# frames_v03.net
KiCad netlist of a schematic drawn in EAGLE
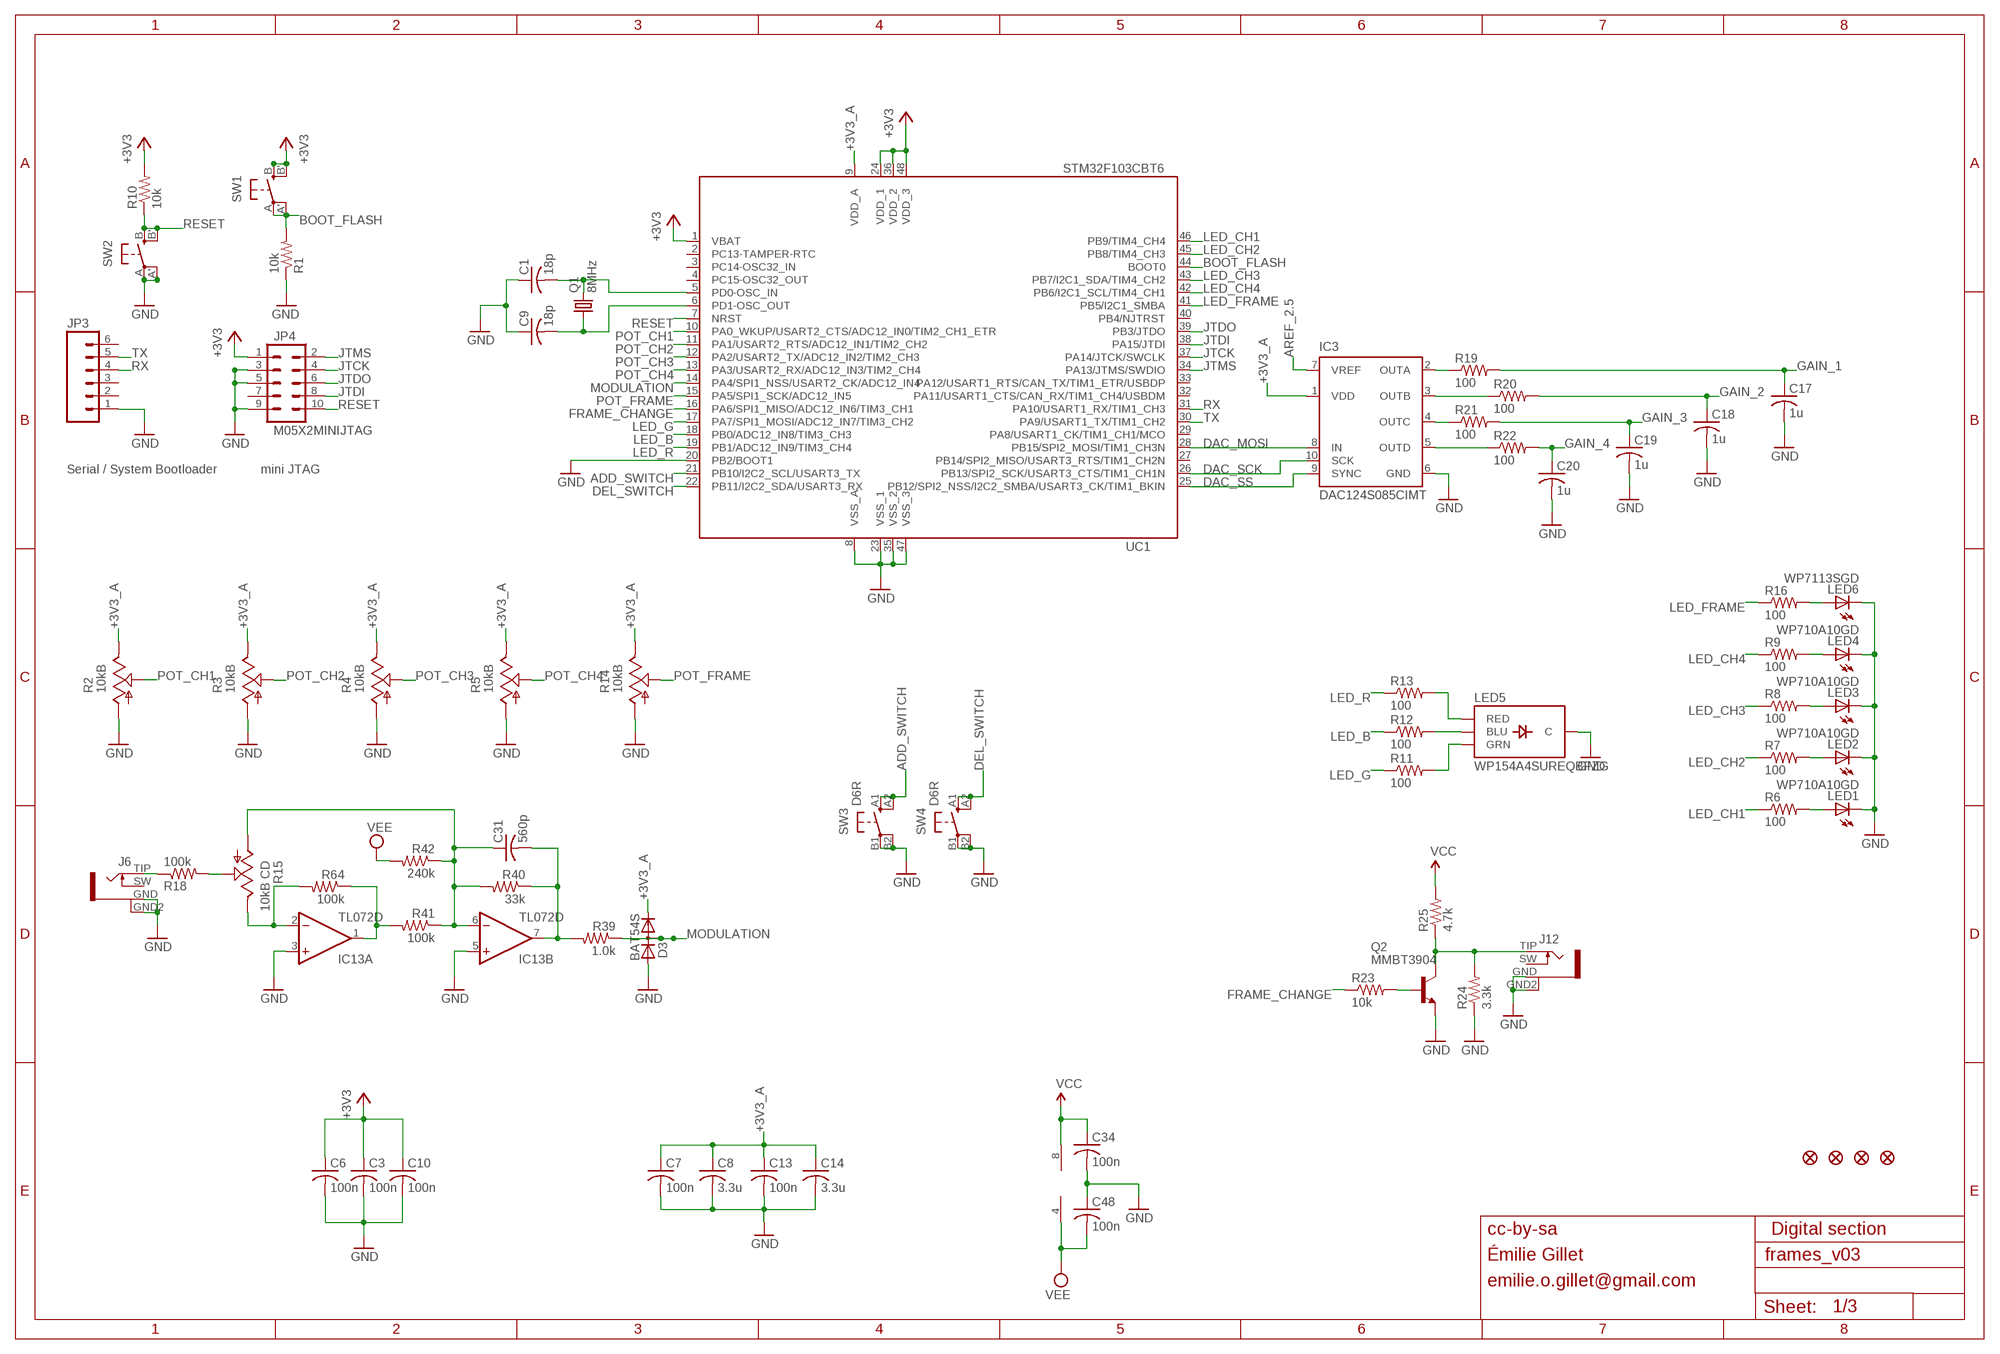
[diagram p0: schematic, sheet 1]
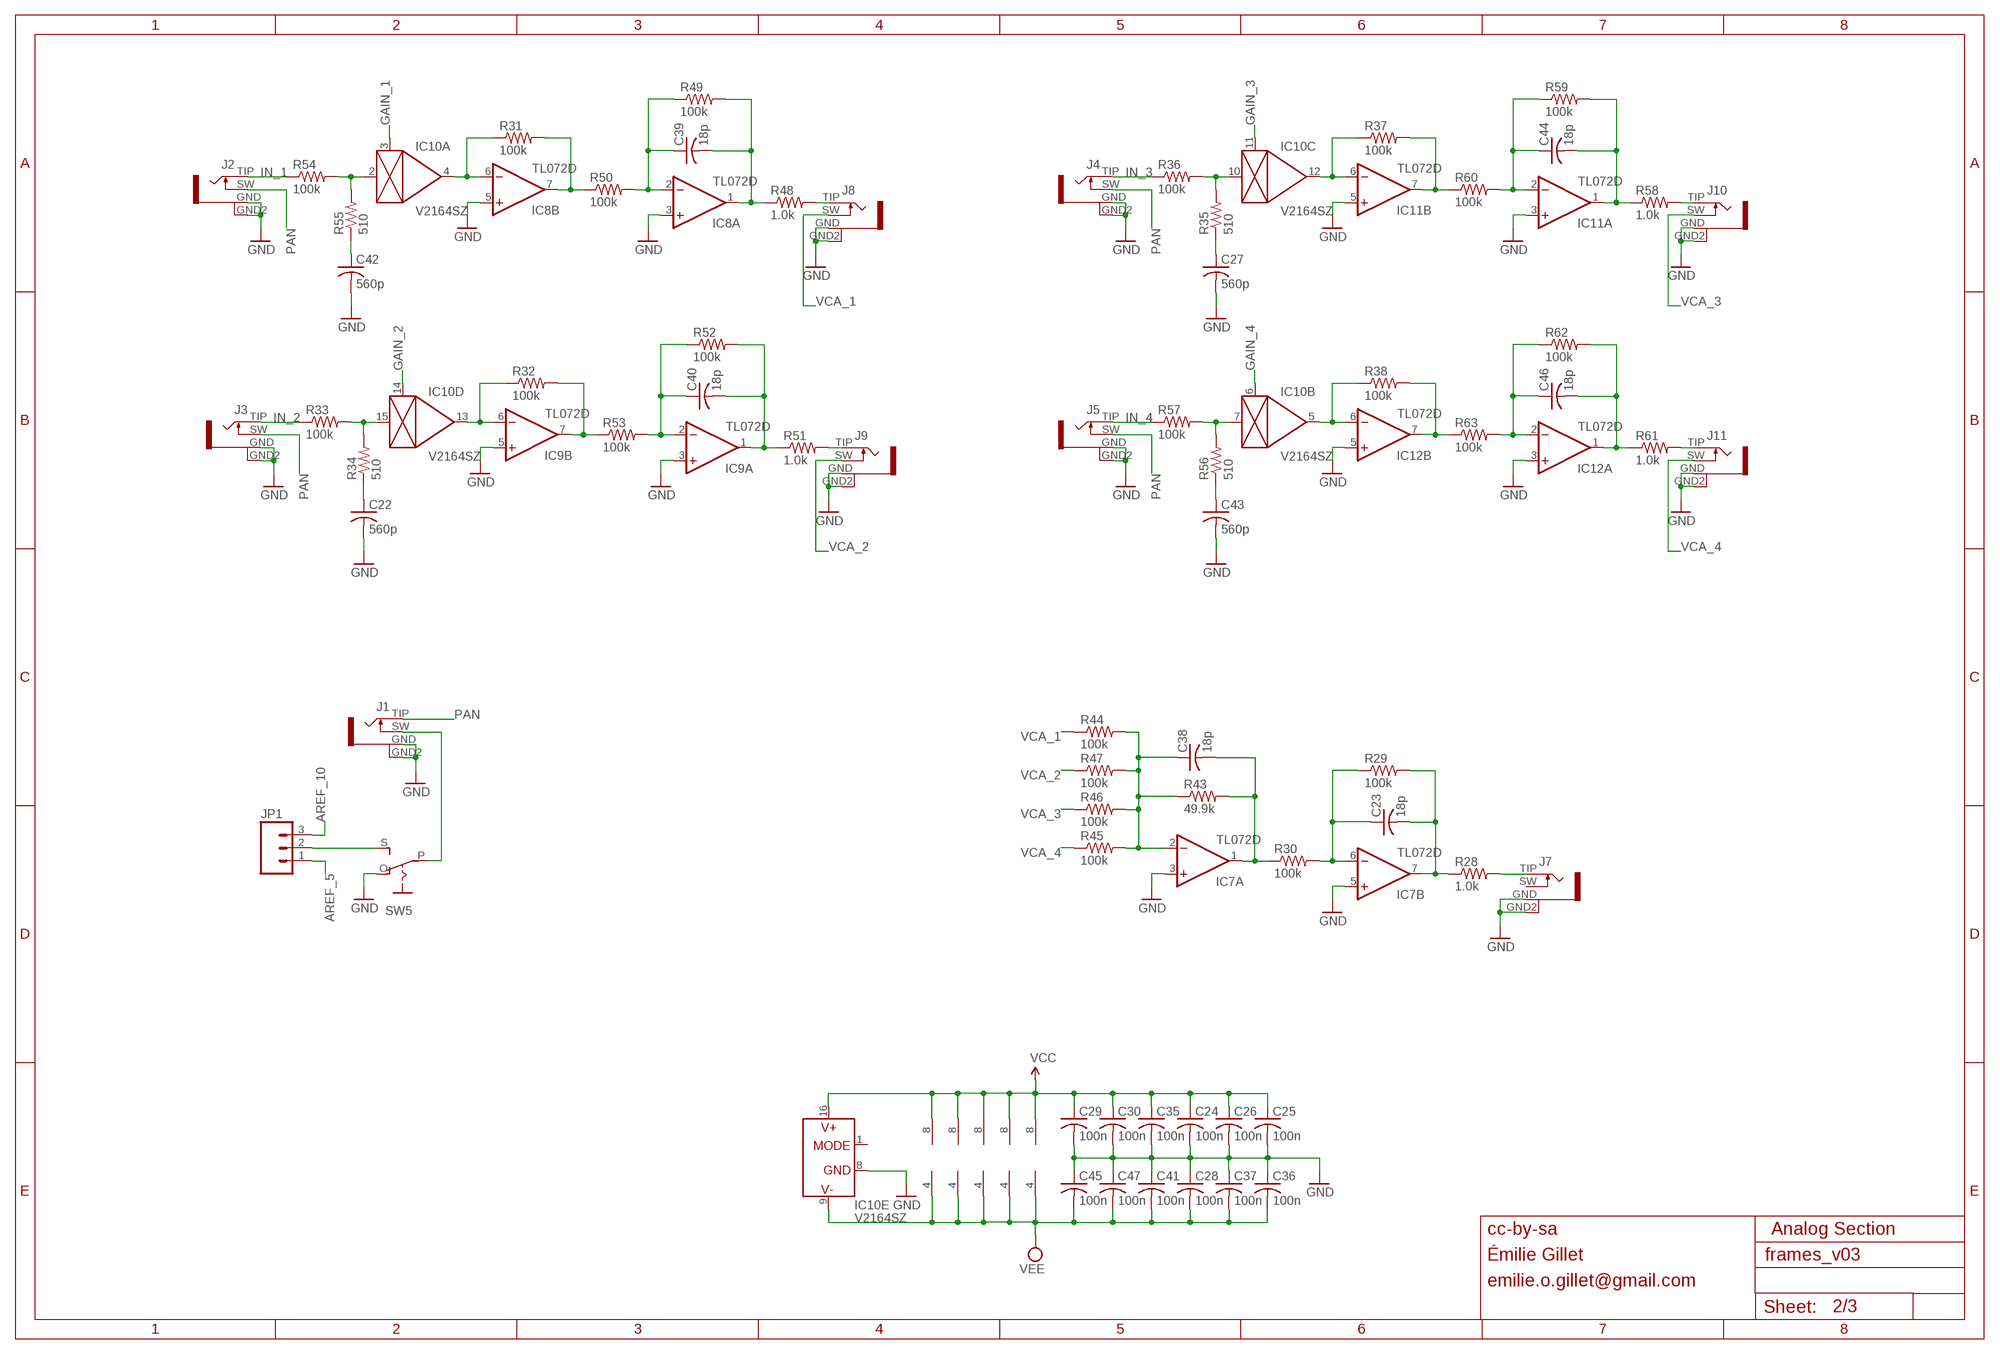
[diagram p1: schematic, sheet 2]
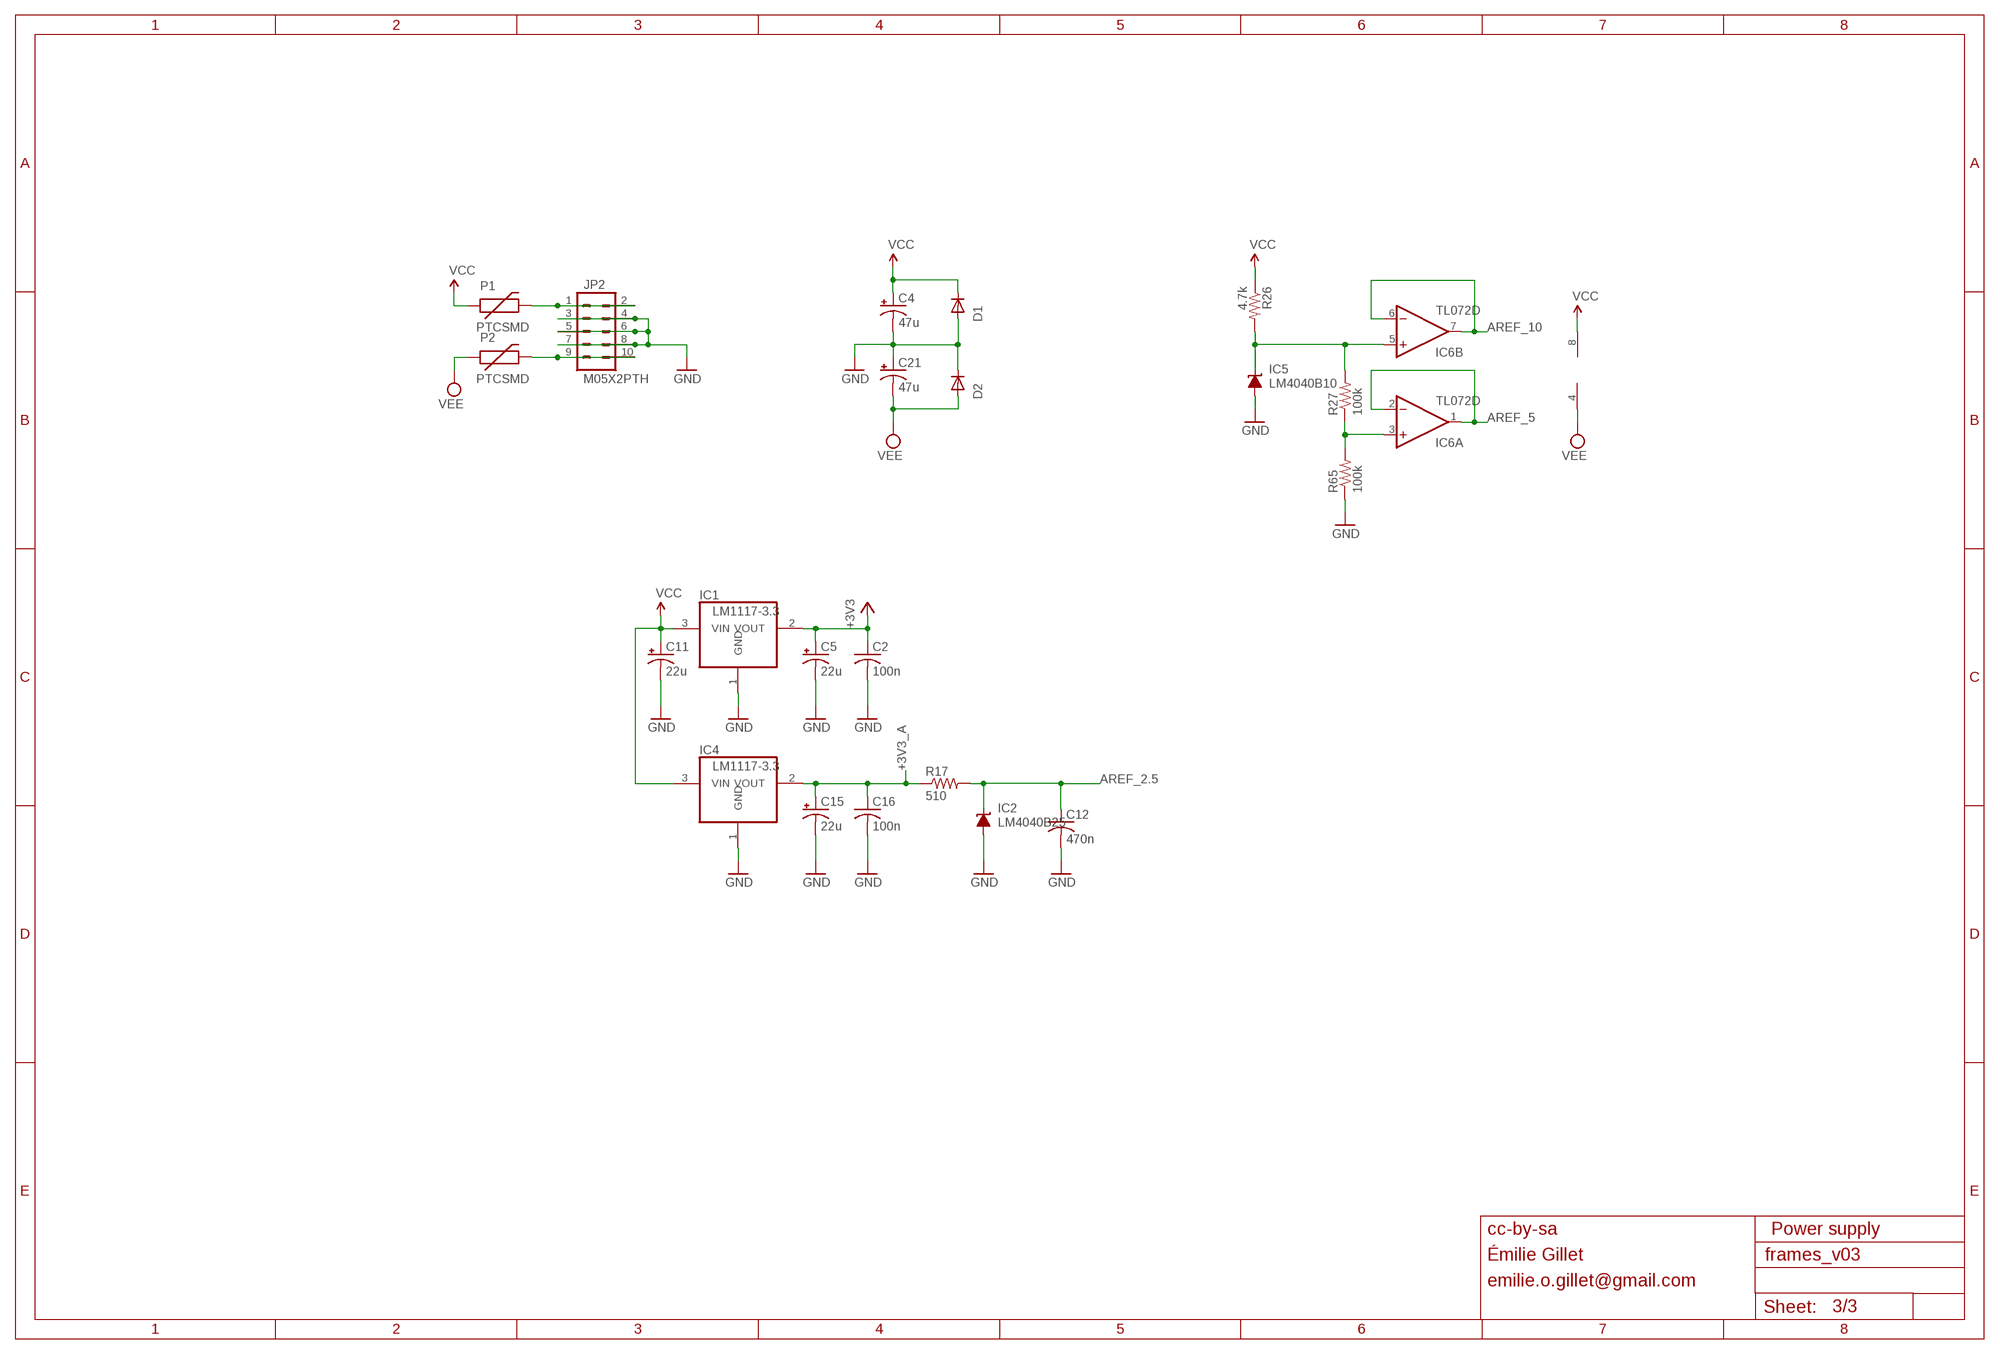
[diagram p2: schematic, sheet 3]

(export (version "E")
  (design (tool "Eeschema 10.0.6"))
  (components
    (comp (ref "C2")
      (value "100n")
      (footprint "eagle-import:C0603")
      (libsource (lib "eagle-import") (part "C-USC0603"))
    )
    (comp (ref "C4")
      (value "47u")
      (footprint "eagle-import:PANASONIC_D")
      (libsource (lib "eagle-import") (part "CPOL-USD"))
    )
    (comp (ref "C5")
      (value "22u")
      (footprint "eagle-import:PANASONIC_C")
      (libsource (lib "eagle-import") (part "CPOL-USC"))
    )
    (comp (ref "C11")
      (value "22u")
      (footprint "eagle-import:PANASONIC_C")
      (libsource (lib "eagle-import") (part "CPOL-USC"))
    )
    (comp (ref "C12")
      (value "470n")
      (footprint "eagle-import:C0603")
      (libsource (lib "eagle-import") (part "C-USC0603"))
    )
    (comp (ref "C15")
      (value "22u")
      (footprint "eagle-import:PANASONIC_C")
      (libsource (lib "eagle-import") (part "CPOL-USC"))
    )
    (comp (ref "C16")
      (value "100n")
      (footprint "eagle-import:C0603")
      (libsource (lib "eagle-import") (part "C-USC0603"))
    )
    (comp (ref "C21")
      (value "47u")
      (footprint "eagle-import:PANASONIC_D")
      (libsource (lib "eagle-import") (part "CPOL-USD"))
    )
    (comp (ref "D1")
      (value "1N5819HW")
      (footprint "eagle-import:SOD123")
      (libsource (lib "eagle-import") (part "DIODE-SOD123"))
    )
    (comp (ref "D2")
      (value "1N5819HW")
      (footprint "eagle-import:SOD123")
      (libsource (lib "eagle-import") (part "DIODE-SOD123"))
    )
    (comp (ref "IC1")
      (value "LM1117-3.3")
      (footprint "eagle-import:SOT223")
      (libsource (lib "eagle-import") (part "REG1117"))
    )
    (comp (ref "IC2")
      (value "LM4040B25")
      (footprint "eagle-import:DBZ_R-PDSO-G3")
      (libsource (lib "eagle-import") (part "LM4041DBZB12"))
    )
    (comp (ref "IC4")
      (value "LM1117-3.3")
      (footprint "eagle-import:SOT223")
      (libsource (lib "eagle-import") (part "REG1117"))
    )
    (comp (ref "IC5")
      (value "LM4040B10")
      (footprint "eagle-import:DBZ_R-PDSO-G3")
      (libsource (lib "eagle-import") (part "LM4041DBZB12"))
    )
    (comp (ref "IC6")
      (value "TL072D")
      (footprint "eagle-import:SO08")
      (libsource (lib "eagle-import") (part "TL072D"))
    )
    (comp (ref "JP2")
      (value "M05X2PTH")
      (footprint "eagle-import:AVR_ICSP")
      (libsource (lib "eagle-import") (part "M05X2PTH"))
    )
    (comp (ref "P1")
      (value "PTCSMD")
      (footprint "eagle-import:PTC-1206")
      (libsource (lib "eagle-import") (part "PTCSMD"))
    )
    (comp (ref "P2")
      (value "PTCSMD")
      (footprint "eagle-import:PTC-1206")
      (libsource (lib "eagle-import") (part "PTCSMD"))
    )
    (comp (ref "R17")
      (value "510")
      (footprint "eagle-import:R0603")
      (libsource (lib "eagle-import") (part "R-US_R0603"))
    )
    (comp (ref "R26")
      (value "4.7k")
      (footprint "eagle-import:R0603")
      (libsource (lib "eagle-import") (part "R-US_R0603"))
    )
    (comp (ref "R27")
      (value "100k")
      (footprint "eagle-import:R0603")
      (libsource (lib "eagle-import") (part "R-US_R0603"))
    )
    (comp (ref "R65")
      (value "100k")
      (footprint "eagle-import:R0603")
      (libsource (lib "eagle-import") (part "R-US_R0603"))
    )
    (comp (ref "C22")
      (value "560p")
      (footprint "eagle-import:C0603")
      (libsource (lib "eagle-import") (part "C-USC0603"))
    )
    (comp (ref "C23")
      (value "18p")
      (footprint "eagle-import:C0603")
      (libsource (lib "eagle-import") (part "C-USC0603"))
    )
    (comp (ref "C24")
      (value "100n")
      (footprint "eagle-import:C0603")
      (libsource (lib "eagle-import") (part "C-USC0603"))
    )
    (comp (ref "C25")
      (value "100n")
      (footprint "eagle-import:C0603")
      (libsource (lib "eagle-import") (part "C-USC0603"))
    )
    (comp (ref "C26")
      (value "100n")
      (footprint "eagle-import:C0603")
      (libsource (lib "eagle-import") (part "C-USC0603"))
    )
    (comp (ref "C27")
      (value "560p")
      (footprint "eagle-import:C0603")
      (libsource (lib "eagle-import") (part "C-USC0603"))
    )
    (comp (ref "C28")
      (value "100n")
      (footprint "eagle-import:C0603")
      (libsource (lib "eagle-import") (part "C-USC0603"))
    )
    (comp (ref "C29")
      (value "100n")
      (footprint "eagle-import:C0603")
      (libsource (lib "eagle-import") (part "C-USC0603"))
    )
    (comp (ref "C30")
      (value "100n")
      (footprint "eagle-import:C0603")
      (libsource (lib "eagle-import") (part "C-USC0603"))
    )
    (comp (ref "C35")
      (value "100n")
      (footprint "eagle-import:C0603")
      (libsource (lib "eagle-import") (part "C-USC0603"))
    )
    (comp (ref "C36")
      (value "100n")
      (footprint "eagle-import:C0603")
      (libsource (lib "eagle-import") (part "C-USC0603"))
    )
    (comp (ref "C37")
      (value "100n")
      (footprint "eagle-import:C0603")
      (libsource (lib "eagle-import") (part "C-USC0603"))
    )
    (comp (ref "C38")
      (value "18p")
      (footprint "eagle-import:C0603")
      (libsource (lib "eagle-import") (part "C-USC0603"))
    )
    (comp (ref "C39")
      (value "18p")
      (footprint "eagle-import:C0603")
      (libsource (lib "eagle-import") (part "C-USC0603"))
    )
    (comp (ref "C40")
      (value "18p")
      (footprint "eagle-import:C0603")
      (libsource (lib "eagle-import") (part "C-USC0603"))
    )
    (comp (ref "C41")
      (value "100n")
      (footprint "eagle-import:C0603")
      (libsource (lib "eagle-import") (part "C-USC0603"))
    )
    (comp (ref "C42")
      (value "560p")
      (footprint "eagle-import:C0603")
      (libsource (lib "eagle-import") (part "C-USC0603"))
    )
    (comp (ref "C43")
      (value "560p")
      (footprint "eagle-import:C0603")
      (libsource (lib "eagle-import") (part "C-USC0603"))
    )
    (comp (ref "C44")
      (value "18p")
      (footprint "eagle-import:C0603")
      (libsource (lib "eagle-import") (part "C-USC0603"))
    )
    (comp (ref "C45")
      (value "100n")
      (footprint "eagle-import:C0603")
      (libsource (lib "eagle-import") (part "C-USC0603"))
    )
    (comp (ref "C46")
      (value "18p")
      (footprint "eagle-import:C0603")
      (libsource (lib "eagle-import") (part "C-USC0603"))
    )
    (comp (ref "C47")
      (value "100n")
      (footprint "eagle-import:C0603")
      (libsource (lib "eagle-import") (part "C-USC0603"))
    )
    (comp (ref "IC7")
      (value "TL072D")
      (footprint "eagle-import:SO08")
      (libsource (lib "eagle-import") (part "og-linear_TL072D"))
    )
    (comp (ref "IC8")
      (value "TL072D")
      (footprint "eagle-import:SO08")
      (libsource (lib "eagle-import") (part "og-linear_TL072D"))
    )
    (comp (ref "IC9")
      (value "TL072D")
      (footprint "eagle-import:SO08")
      (libsource (lib "eagle-import") (part "og-linear_TL072D"))
    )
    (comp (ref "IC10")
      (value "V2164SZ")
      (footprint "eagle-import:SOIC16N")
      (libsource (lib "eagle-import") (part "SSM2164S"))
    )
    (comp (ref "IC11")
      (value "TL072D")
      (footprint "eagle-import:SO08")
      (libsource (lib "eagle-import") (part "og-linear_TL072D"))
    )
    (comp (ref "IC12")
      (value "TL072D")
      (footprint "eagle-import:SO08")
      (libsource (lib "eagle-import") (part "og-linear_TL072D"))
    )
    (comp (ref "J1")
      (value "PJ301WQP")
      (footprint "eagle-import:WQP_PJ_301BM")
      (libsource (lib "eagle-import") (part "PJ301WQP"))
    )
    (comp (ref "J2")
      (value "PJ301WQP")
      (footprint "eagle-import:WQP_PJ_301BM")
      (libsource (lib "eagle-import") (part "PJ301WQP"))
    )
    (comp (ref "J3")
      (value "PJ301WQP")
      (footprint "eagle-import:WQP_PJ_301BM")
      (libsource (lib "eagle-import") (part "PJ301WQP"))
    )
    (comp (ref "J4")
      (value "PJ301WQP")
      (footprint "eagle-import:WQP_PJ_301BM")
      (libsource (lib "eagle-import") (part "PJ301WQP"))
    )
    (comp (ref "J5")
      (value "PJ301WQP")
      (footprint "eagle-import:WQP_PJ_301BM")
      (libsource (lib "eagle-import") (part "PJ301WQP"))
    )
    (comp (ref "J7")
      (value "PJ301WQP")
      (footprint "eagle-import:WQP_PJ_301BM")
      (libsource (lib "eagle-import") (part "PJ301WQP"))
    )
    (comp (ref "J8")
      (value "PJ301WQP")
      (footprint "eagle-import:WQP_PJ_301BM")
      (libsource (lib "eagle-import") (part "PJ301WQP"))
    )
    (comp (ref "J9")
      (value "PJ301WQP")
      (footprint "eagle-import:WQP_PJ_301BM")
      (libsource (lib "eagle-import") (part "PJ301WQP"))
    )
    (comp (ref "J10")
      (value "PJ301WQP")
      (footprint "eagle-import:WQP_PJ_301BM")
      (libsource (lib "eagle-import") (part "PJ301WQP"))
    )
    (comp (ref "J11")
      (value "PJ301WQP")
      (footprint "eagle-import:WQP_PJ_301BM")
      (libsource (lib "eagle-import") (part "PJ301WQP"))
    )
    (comp (ref "JP1")
      (value "M03PTH")
      (footprint "eagle-import:1X03")
      (libsource (lib "eagle-import") (part "M03PTH"))
    )
    (comp (ref "R28")
      (value "1.0k")
      (footprint "eagle-import:R0603")
      (libsource (lib "eagle-import") (part "R-US_R0603"))
    )
    (comp (ref "R29")
      (value "100k")
      (footprint "eagle-import:R0603")
      (libsource (lib "eagle-import") (part "R-US_R0603"))
    )
    (comp (ref "R30")
      (value "100k")
      (footprint "eagle-import:R0603")
      (libsource (lib "eagle-import") (part "R-US_R0603"))
    )
    (comp (ref "R31")
      (value "100k")
      (footprint "eagle-import:R0603")
      (libsource (lib "eagle-import") (part "R-US_R0603"))
    )
    (comp (ref "R32")
      (value "100k")
      (footprint "eagle-import:R0603")
      (libsource (lib "eagle-import") (part "R-US_R0603"))
    )
    (comp (ref "R33")
      (value "100k")
      (footprint "eagle-import:R0603")
      (libsource (lib "eagle-import") (part "R-US_R0603"))
    )
    (comp (ref "R34")
      (value "510")
      (footprint "eagle-import:R0603")
      (libsource (lib "eagle-import") (part "R-US_R0603"))
    )
    (comp (ref "R35")
      (value "510")
      (footprint "eagle-import:R0603")
      (libsource (lib "eagle-import") (part "R-US_R0603"))
    )
    (comp (ref "R36")
      (value "100k")
      (footprint "eagle-import:R0603")
      (libsource (lib "eagle-import") (part "R-US_R0603"))
    )
    (comp (ref "R37")
      (value "100k")
      (footprint "eagle-import:R0603")
      (libsource (lib "eagle-import") (part "R-US_R0603"))
    )
    (comp (ref "R38")
      (value "100k")
      (footprint "eagle-import:R0603")
      (libsource (lib "eagle-import") (part "R-US_R0603"))
    )
    (comp (ref "R43")
      (value "49.9k")
      (footprint "eagle-import:R0603")
      (libsource (lib "eagle-import") (part "R-US_R0603"))
    )
    (comp (ref "R44")
      (value "100k")
      (footprint "eagle-import:R0603")
      (libsource (lib "eagle-import") (part "R-US_R0603"))
    )
    (comp (ref "R45")
      (value "100k")
      (footprint "eagle-import:R0603")
      (libsource (lib "eagle-import") (part "R-US_R0603"))
    )
    (comp (ref "R46")
      (value "100k")
      (footprint "eagle-import:R0603")
      (libsource (lib "eagle-import") (part "R-US_R0603"))
    )
    (comp (ref "R47")
      (value "100k")
      (footprint "eagle-import:R0603")
      (libsource (lib "eagle-import") (part "R-US_R0603"))
    )
    (comp (ref "R48")
      (value "1.0k")
      (footprint "eagle-import:R0603")
      (libsource (lib "eagle-import") (part "R-US_R0603"))
    )
    (comp (ref "R49")
      (value "100k")
      (footprint "eagle-import:R0603")
      (libsource (lib "eagle-import") (part "R-US_R0603"))
    )
    (comp (ref "R50")
      (value "100k")
      (footprint "eagle-import:R0603")
      (libsource (lib "eagle-import") (part "R-US_R0603"))
    )
    (comp (ref "R51")
      (value "1.0k")
      (footprint "eagle-import:R0603")
      (libsource (lib "eagle-import") (part "R-US_R0603"))
    )
    (comp (ref "R52")
      (value "100k")
      (footprint "eagle-import:R0603")
      (libsource (lib "eagle-import") (part "R-US_R0603"))
    )
    (comp (ref "R53")
      (value "100k")
      (footprint "eagle-import:R0603")
      (libsource (lib "eagle-import") (part "R-US_R0603"))
    )
    (comp (ref "R54")
      (value "100k")
      (footprint "eagle-import:R0603")
      (libsource (lib "eagle-import") (part "R-US_R0603"))
    )
    (comp (ref "R55")
      (value "510")
      (footprint "eagle-import:R0603")
      (libsource (lib "eagle-import") (part "R-US_R0603"))
    )
    (comp (ref "R56")
      (value "510")
      (footprint "eagle-import:R0603")
      (libsource (lib "eagle-import") (part "R-US_R0603"))
    )
    (comp (ref "R57")
      (value "100k")
      (footprint "eagle-import:R0603")
      (libsource (lib "eagle-import") (part "R-US_R0603"))
    )
    (comp (ref "R58")
      (value "1.0k")
      (footprint "eagle-import:R0603")
      (libsource (lib "eagle-import") (part "R-US_R0603"))
    )
    (comp (ref "R59")
      (value "100k")
      (footprint "eagle-import:R0603")
      (libsource (lib "eagle-import") (part "R-US_R0603"))
    )
    (comp (ref "R60")
      (value "100k")
      (footprint "eagle-import:R0603")
      (libsource (lib "eagle-import") (part "R-US_R0603"))
    )
    (comp (ref "R61")
      (value "1.0k")
      (footprint "eagle-import:R0603")
      (libsource (lib "eagle-import") (part "R-US_R0603"))
    )
    (comp (ref "R62")
      (value "100k")
      (footprint "eagle-import:R0603")
      (libsource (lib "eagle-import") (part "R-US_R0603"))
    )
    (comp (ref "R63")
      (value "100k")
      (footprint "eagle-import:R0603")
      (libsource (lib "eagle-import") (part "R-US_R0603"))
    )
    (comp (ref "SW5")
      (value "S-ON-ONSMALL_SLIDE")
      (footprint "eagle-import:ES_100SP1T6B11M2QEH_SMALL")
      (libsource (lib "eagle-import") (part "S-ON-ONSMALL_SLIDE"))
    )
    (comp (ref "C1")
      (value "18p")
      (footprint "eagle-import:C0603")
      (libsource (lib "eagle-import") (part "C-USC0603"))
    )
    (comp (ref "C3")
      (value "100n")
      (footprint "eagle-import:C0603")
      (libsource (lib "eagle-import") (part "C-USC0603"))
    )
    (comp (ref "C6")
      (value "100n")
      (footprint "eagle-import:C0603")
      (libsource (lib "eagle-import") (part "C-USC0603"))
    )
    (comp (ref "C7")
      (value "100n")
      (footprint "eagle-import:C0603")
      (libsource (lib "eagle-import") (part "C-USC0603"))
    )
    (comp (ref "C8")
      (value "3.3u")
      (footprint "eagle-import:C0603")
      (libsource (lib "eagle-import") (part "C-USC0603"))
    )
    (comp (ref "C9")
      (value "18p")
      (footprint "eagle-import:C0603")
      (libsource (lib "eagle-import") (part "C-USC0603"))
    )
    (comp (ref "C10")
      (value "100n")
      (footprint "eagle-import:C0603")
      (libsource (lib "eagle-import") (part "C-USC0603"))
    )
    (comp (ref "C13")
      (value "100n")
      (footprint "eagle-import:C0603")
      (libsource (lib "eagle-import") (part "C-USC0603"))
    )
    (comp (ref "C14")
      (value "3.3u")
      (footprint "eagle-import:C0603")
      (libsource (lib "eagle-import") (part "C-USC0603"))
    )
    (comp (ref "C17")
      (value "1u")
      (footprint "eagle-import:C0603")
      (libsource (lib "eagle-import") (part "C-USC0603"))
    )
    (comp (ref "C18")
      (value "1u")
      (footprint "eagle-import:C0603")
      (libsource (lib "eagle-import") (part "C-USC0603"))
    )
    (comp (ref "C19")
      (value "1u")
      (footprint "eagle-import:C0603")
      (libsource (lib "eagle-import") (part "C-USC0603"))
    )
    (comp (ref "C20")
      (value "1u")
      (footprint "eagle-import:C0603")
      (libsource (lib "eagle-import") (part "C-USC0603"))
    )
    (comp (ref "C31")
      (value "560p")
      (footprint "eagle-import:C0603")
      (libsource (lib "eagle-import") (part "C-USC0603"))
    )
    (comp (ref "C34")
      (value "100n")
      (footprint "eagle-import:C0603")
      (libsource (lib "eagle-import") (part "C-USC0603"))
    )
    (comp (ref "C48")
      (value "100n")
      (footprint "eagle-import:C0603")
      (libsource (lib "eagle-import") (part "C-USC0603"))
    )
    (comp (ref "D3")
      (value "BAT54S")
      (footprint "eagle-import:SOT23")
      (libsource (lib "eagle-import") (part "DIODE_2CACA-SOT23"))
    )
    (comp (ref "F1")
      (value "FIDUCIAL1X2")
      (footprint "eagle-import:FIDUCIAL-1X2")
      (libsource (lib "eagle-import") (part "FIDUCIAL1X2"))
    )
    (comp (ref "F2")
      (value "FIDUCIAL1X2")
      (footprint "eagle-import:FIDUCIAL-1X2")
      (libsource (lib "eagle-import") (part "FIDUCIAL1X2"))
    )
    (comp (ref "F3")
      (value "FIDUCIAL1X2")
      (footprint "eagle-import:FIDUCIAL-1X2")
      (libsource (lib "eagle-import") (part "FIDUCIAL1X2"))
    )
    (comp (ref "F4")
      (value "FIDUCIAL1X2")
      (footprint "eagle-import:FIDUCIAL-1X2")
      (libsource (lib "eagle-import") (part "FIDUCIAL1X2"))
    )
    (comp (ref "IC3")
      (value "DAC124S085CIMT")
      (footprint "eagle-import:MSOP10")
      (libsource (lib "eagle-import") (part "DAC124S085CIMT"))
    )
    (comp (ref "IC13")
      (value "TL072D")
      (footprint "eagle-import:SO08")
      (libsource (lib "eagle-import") (part "og-linear_TL072D"))
    )
    (comp (ref "J6")
      (value "PJ301WQP")
      (footprint "eagle-import:WQP_PJ_301BM")
      (libsource (lib "eagle-import") (part "PJ301WQP"))
    )
    (comp (ref "J12")
      (value "PJ301WQP")
      (footprint "eagle-import:WQP_PJ_301BM")
      (libsource (lib "eagle-import") (part "PJ301WQP"))
    )
    (comp (ref "JP3")
      (value "M06SIP")
      (footprint "eagle-import:1X06")
      (libsource (lib "eagle-import") (part "M06SIP"))
    )
    (comp (ref "JP4")
      (value "M05X2MINIJTAG")
      (footprint "eagle-import:2X5-1.27")
      (libsource (lib "eagle-import") (part "M05X2MINIJTAG"))
    )
    (comp (ref "LED1")
      (value "WP710A10GD")
      (footprint "eagle-import:LED3MM")
      (libsource (lib "eagle-import") (part "LED3MM"))
    )
    (comp (ref "LED2")
      (value "WP710A10GD")
      (footprint "eagle-import:LED3MM")
      (libsource (lib "eagle-import") (part "LED3MM"))
    )
    (comp (ref "LED3")
      (value "WP710A10GD")
      (footprint "eagle-import:LED3MM")
      (libsource (lib "eagle-import") (part "LED3MM"))
    )
    (comp (ref "LED4")
      (value "WP710A10GD")
      (footprint "eagle-import:LED3MM")
      (libsource (lib "eagle-import") (part "LED3MM"))
    )
    (comp (ref "LED5")
      (value "WP154A4SUREQBFZG")
      (footprint "eagle-import:LED-TRICOLOR-THROUGHHOLE")
      (libsource (lib "eagle-import") (part "LED-TRICOLOR-THROUGHHOLE"))
    )
    (comp (ref "LED6")
      (value "WP7113SGD")
      (footprint "eagle-import:LED5MM")
      (libsource (lib "eagle-import") (part "LED5MM"))
    )
    (comp (ref "Q1")
      (value "8MHz")
      (footprint "eagle-import:HC49UP")
      (libsource (lib "eagle-import") (part "CRYSTALHC49UP"))
    )
    (comp (ref "Q2")
      (value "MMBT3904")
      (footprint "eagle-import:SOT23-BEC")
      (libsource (lib "eagle-import") (part "-NPN-SOT23-BECMMBT3904LT1"))
    )
    (comp (ref "R1")
      (value "10k")
      (footprint "eagle-import:R0603")
      (libsource (lib "eagle-import") (part "R-US_R0603"))
    )
    (comp (ref "R2")
      (value "10kB")
      (footprint "eagle-import:ALPS_POT_VERTICAL_PS")
      (libsource (lib "eagle-import") (part "POT_USVERTICAL_PS"))
    )
    (comp (ref "R3")
      (value "10kB")
      (footprint "eagle-import:ALPS_POT_VERTICAL_PS")
      (libsource (lib "eagle-import") (part "POT_USVERTICAL_PS"))
    )
    (comp (ref "R4")
      (value "10kB")
      (footprint "eagle-import:ALPS_POT_VERTICAL_PS")
      (libsource (lib "eagle-import") (part "POT_USVERTICAL_PS"))
    )
    (comp (ref "R5")
      (value "10kB")
      (footprint "eagle-import:ALPS_POT_VERTICAL_PS")
      (libsource (lib "eagle-import") (part "POT_USVERTICAL_PS"))
    )
    (comp (ref "R6")
      (value "100")
      (footprint "eagle-import:R0603")
      (libsource (lib "eagle-import") (part "R-US_R0603"))
    )
    (comp (ref "R7")
      (value "100")
      (footprint "eagle-import:R0603")
      (libsource (lib "eagle-import") (part "R-US_R0603"))
    )
    (comp (ref "R8")
      (value "100")
      (footprint "eagle-import:R0603")
      (libsource (lib "eagle-import") (part "R-US_R0603"))
    )
    (comp (ref "R9")
      (value "100")
      (footprint "eagle-import:R0603")
      (libsource (lib "eagle-import") (part "R-US_R0603"))
    )
    (comp (ref "R10")
      (value "10k")
      (footprint "eagle-import:R0603")
      (libsource (lib "eagle-import") (part "R-US_R0603"))
    )
    (comp (ref "R11")
      (value "100")
      (footprint "eagle-import:R0603")
      (libsource (lib "eagle-import") (part "R-US_R0603"))
    )
    (comp (ref "R12")
      (value "100")
      (footprint "eagle-import:R0603")
      (libsource (lib "eagle-import") (part "R-US_R0603"))
    )
    (comp (ref "R13")
      (value "100")
      (footprint "eagle-import:R0603")
      (libsource (lib "eagle-import") (part "R-US_R0603"))
    )
    (comp (ref "R14")
      (value "10kB")
      (footprint "eagle-import:ALPS_POT_VERTICAL_PS")
      (libsource (lib "eagle-import") (part "POT_USVERTICAL_PS"))
    )
    (comp (ref "R15")
      (value "10kB CD")
      (footprint "eagle-import:ALPS_POT_VERTICAL_PS")
      (libsource (lib "eagle-import") (part "POT_USVERTICAL_PS"))
    )
    (comp (ref "R16")
      (value "100")
      (footprint "eagle-import:R0603")
      (libsource (lib "eagle-import") (part "R-US_R0603"))
    )
    (comp (ref "R18")
      (value "100k")
      (footprint "eagle-import:R0603")
      (libsource (lib "eagle-import") (part "R-US_R0603"))
    )
    (comp (ref "R19")
      (value "100")
      (footprint "eagle-import:R0603")
      (libsource (lib "eagle-import") (part "R-US_R0603"))
    )
    (comp (ref "R20")
      (value "100")
      (footprint "eagle-import:R0603")
      (libsource (lib "eagle-import") (part "R-US_R0603"))
    )
    (comp (ref "R21")
      (value "100")
      (footprint "eagle-import:R0603")
      (libsource (lib "eagle-import") (part "R-US_R0603"))
    )
    (comp (ref "R22")
      (value "100")
      (footprint "eagle-import:R0603")
      (libsource (lib "eagle-import") (part "R-US_R0603"))
    )
    (comp (ref "R23")
      (value "10k")
      (footprint "eagle-import:R0603")
      (libsource (lib "eagle-import") (part "R-US_R0603"))
    )
    (comp (ref "R24")
      (value "3.3k")
      (footprint "eagle-import:R0603")
      (libsource (lib "eagle-import") (part "R-US_R0603"))
    )
    (comp (ref "R25")
      (value "4.7k")
      (footprint "eagle-import:R0603")
      (libsource (lib "eagle-import") (part "R-US_R0603"))
    )
    (comp (ref "R39")
      (value "1.0k")
      (footprint "eagle-import:R0603")
      (libsource (lib "eagle-import") (part "R-US_R0603"))
    )
    (comp (ref "R40")
      (value "33k")
      (footprint "eagle-import:R0603")
      (libsource (lib "eagle-import") (part "R-US_R0603"))
    )
    (comp (ref "R41")
      (value "100k")
      (footprint "eagle-import:R0603")
      (libsource (lib "eagle-import") (part "R-US_R0603"))
    )
    (comp (ref "R42")
      (value "240k")
      (footprint "eagle-import:R0603")
      (libsource (lib "eagle-import") (part "R-US_R0603"))
    )
    (comp (ref "R64")
      (value "100k")
      (footprint "eagle-import:R0603")
      (libsource (lib "eagle-import") (part "R-US_R0603"))
    )
    (comp (ref "SW1")
      (value "EVQQ2")
      (footprint "eagle-import:EVQ-Q2")
      (libsource (lib "eagle-import") (part "EVQQ2"))
    )
    (comp (ref "SW2")
      (value "EVQQ2")
      (footprint "eagle-import:EVQ-Q2")
      (libsource (lib "eagle-import") (part "EVQQ2"))
    )
    (comp (ref "SW3")
      (value "D6R")
      (footprint "eagle-import:D6R")
      (libsource (lib "eagle-import") (part "D6R"))
    )
    (comp (ref "SW4")
      (value "D6R")
      (footprint "eagle-import:D6R")
      (libsource (lib "eagle-import") (part "D6R"))
    )
    (comp (ref "UC1")
      (value "STM32F103CBT6")
      (footprint "eagle-import:LQFP48")
      (libsource (lib "eagle-import") (part "STM32F103CB"))
    )
  )
  (nets
    (net (code "1") (name "+3V3") (class "Default")
      (node (ref "C10") (pin "1") (pinfunction "1_1") (pintype "passive"))
      (node (ref "C2") (pin "1") (pinfunction "1_1") (pintype "passive"))
      (node (ref "C3") (pin "1") (pinfunction "1_1") (pintype "passive"))
      (node (ref "C5") (pin "+") (pinfunction "+_+") (pintype "passive"))
      (node (ref "C6") (pin "1") (pinfunction "1_1") (pintype "passive"))
      (node (ref "IC1") (pin "2") (pinfunction "VOUT_2") (pintype "output"))
      (node (ref "JP4") (pin "1") (pinfunction "1_1") (pintype "passive"))
      (node (ref "R10") (pin "2") (pinfunction "2_2") (pintype "passive"))
      (node (ref "SW1") (pin "B") (pinfunction "S_B") (pintype "passive"))
      (node (ref "SW1") (pin "B'") (pinfunction "S1_B'") (pintype "passive"))
      (node (ref "UC1") (pin "1") (pinfunction "VBAT_1") (pintype "power_in"))
      (node (ref "UC1") (pin "24") (pinfunction "VDD_1_24") (pintype "power_in"))
      (node (ref "UC1") (pin "36") (pinfunction "VDD_2_36") (pintype "power_in"))
      (node (ref "UC1") (pin "48") (pinfunction "VDD_3_48") (pintype "power_in"))
    )
    (net (code "2") (name "+3V3_A") (class "Default")
      (node (ref "C13") (pin "1") (pinfunction "1_1") (pintype "passive"))
      (node (ref "C14") (pin "1") (pinfunction "1_1") (pintype "passive"))
      (node (ref "C15") (pin "+") (pinfunction "+_+") (pintype "passive"))
      (node (ref "C16") (pin "1") (pinfunction "1_1") (pintype "passive"))
      (node (ref "C7") (pin "1") (pinfunction "1_1") (pintype "passive"))
      (node (ref "C8") (pin "1") (pinfunction "1_1") (pintype "passive"))
      (node (ref "D3") (pin "2") (pinfunction "C_2") (pintype "passive"))
      (node (ref "IC3") (pin "1") (pinfunction "VDD_1") (pintype "power_in"))
      (node (ref "IC4") (pin "2") (pinfunction "VOUT_2") (pintype "output"))
      (node (ref "R14") (pin "P$1") (pinfunction "E_P$1") (pintype "passive"))
      (node (ref "R17") (pin "1") (pinfunction "1_1") (pintype "passive"))
      (node (ref "R2") (pin "P$1") (pinfunction "E_P$1") (pintype "passive"))
      (node (ref "R3") (pin "P$1") (pinfunction "E_P$1") (pintype "passive"))
      (node (ref "R4") (pin "P$1") (pinfunction "E_P$1") (pintype "passive"))
      (node (ref "R5") (pin "P$1") (pinfunction "E_P$1") (pintype "passive"))
      (node (ref "UC1") (pin "9") (pinfunction "VDD_A_9") (pintype "power_in"))
    )
    (net (code "3") (name "ADD_SWITCH") (class "Default")
      (node (ref "SW3") (pin "A1") (pinfunction "S_A1") (pintype "passive"))
      (node (ref "SW3") (pin "A2") (pinfunction "S1_A2") (pintype "passive"))
      (node (ref "UC1") (pin "21") (pinfunction "PB10/I2C2_SCL/USART3_TX_21") (pintype "input"))
    )
    (net (code "4") (name "AREF_2.5") (class "Default")
      (node (ref "C12") (pin "1") (pinfunction "1_1") (pintype "passive"))
      (node (ref "IC2") (pin "1") (pinfunction "C_1") (pintype "passive"))
      (node (ref "IC3") (pin "7") (pinfunction "VREF_7") (pintype "bidirectional"))
      (node (ref "R17") (pin "2") (pinfunction "2_2") (pintype "passive"))
    )
    (net (code "5") (name "AREF_5") (class "Default")
      (node (ref "IC6") (pin "1") (pinfunction "OUT_1") (pintype "output"))
      (node (ref "IC6") (pin "2") (pinfunction "-IN_2") (pintype "input"))
      (node (ref "JP1") (pin "1") (pinfunction "1_1") (pintype "passive"))
    )
    (net (code "6") (name "AREF_10") (class "Default")
      (node (ref "IC6") (pin "6") (pinfunction "-IN_6") (pintype "input"))
      (node (ref "IC6") (pin "7") (pinfunction "OUT_7") (pintype "output"))
      (node (ref "JP1") (pin "3") (pinfunction "3_3") (pintype "passive"))
    )
    (net (code "7") (name "BOOT_FLASH") (class "Default")
      (node (ref "R1") (pin "2") (pinfunction "2_2") (pintype "passive"))
      (node (ref "SW1") (pin "A") (pinfunction "P_A") (pintype "passive"))
      (node (ref "SW1") (pin "A'") (pinfunction "P1_A'") (pintype "passive"))
      (node (ref "UC1") (pin "44") (pinfunction "BOOT0_44") (pintype "input"))
    )
    (net (code "8") (name "DAC_MOSI") (class "Default")
      (node (ref "IC3") (pin "8") (pinfunction "IN_8") (pintype "input"))
      (node (ref "UC1") (pin "28") (pinfunction "PB15/SPI2_MOSI/TIM1_CH3N_28") (pintype "input"))
    )
    (net (code "9") (name "DAC_SCK") (class "Default")
      (node (ref "IC3") (pin "10") (pinfunction "SCK_10") (pintype "input"))
      (node (ref "UC1") (pin "26") (pinfunction "PB13/SPI2_SCK/USART3_CTS/TIM1_CH1N_26") (pintype "input"))
    )
    (net (code "10") (name "DAC_SS") (class "Default")
      (node (ref "IC3") (pin "9") (pinfunction "SYNC_9") (pintype "input"))
      (node (ref "UC1") (pin "25") (pinfunction "PB12/SPI2_NSS/I2C2_SMBA/USART3_CK/TIM1_BKIN_25") (pintype "input"))
    )
    (net (code "11") (name "DEL_SWITCH") (class "Default")
      (node (ref "SW4") (pin "A1") (pinfunction "S_A1") (pintype "passive"))
      (node (ref "SW4") (pin "A2") (pinfunction "S1_A2") (pintype "passive"))
      (node (ref "UC1") (pin "22") (pinfunction "PB11/I2C2_SDA/USART3_RX_22") (pintype "input"))
    )
    (net (code "12") (name "FRAME_CHANGE") (class "Default")
      (node (ref "R23") (pin "1") (pinfunction "1_1") (pintype "passive"))
      (node (ref "UC1") (pin "16") (pinfunction "PA6/SPI1_MISO/ADC12_IN6/TIM3_CH1_16") (pintype "bidirectional"))
    )
    (net (code "13") (name "GAIN_1") (class "Default")
      (node (ref "C17") (pin "1") (pinfunction "1_1") (pintype "passive"))
      (node (ref "IC10") (pin "3") (pinfunction "CTRL_3") (pintype "input"))
      (node (ref "R19") (pin "2") (pinfunction "2_2") (pintype "passive"))
    )
    (net (code "14") (name "GAIN_2") (class "Default")
      (node (ref "C18") (pin "1") (pinfunction "1_1") (pintype "passive"))
      (node (ref "IC10") (pin "14") (pinfunction "CTRL_14") (pintype "input"))
      (node (ref "R20") (pin "2") (pinfunction "2_2") (pintype "passive"))
    )
    (net (code "15") (name "GAIN_3") (class "Default")
      (node (ref "C19") (pin "1") (pinfunction "1_1") (pintype "passive"))
      (node (ref "IC10") (pin "11") (pinfunction "CTRL_11") (pintype "input"))
      (node (ref "R21") (pin "2") (pinfunction "2_2") (pintype "passive"))
    )
    (net (code "16") (name "GAIN_4") (class "Default")
      (node (ref "C20") (pin "1") (pinfunction "1_1") (pintype "passive"))
      (node (ref "IC10") (pin "6") (pinfunction "CTRL_6") (pintype "input"))
      (node (ref "R22") (pin "2") (pinfunction "2_2") (pintype "passive"))
    )
    (net (code "17") (name "GND") (class "Default")
      (node (ref "C1") (pin "1") (pinfunction "1_1") (pintype "passive"))
      (node (ref "C10") (pin "2") (pinfunction "2_2") (pintype "passive"))
      (node (ref "C11") (pin "-") (pinfunction "-_-") (pintype "passive"))
      (node (ref "C12") (pin "2") (pinfunction "2_2") (pintype "passive"))
      (node (ref "C13") (pin "2") (pinfunction "2_2") (pintype "passive"))
      (node (ref "C14") (pin "2") (pinfunction "2_2") (pintype "passive"))
      (node (ref "C15") (pin "-") (pinfunction "-_-") (pintype "passive"))
      (node (ref "C16") (pin "2") (pinfunction "2_2") (pintype "passive"))
      (node (ref "C17") (pin "2") (pinfunction "2_2") (pintype "passive"))
      (node (ref "C18") (pin "2") (pinfunction "2_2") (pintype "passive"))
      (node (ref "C19") (pin "2") (pinfunction "2_2") (pintype "passive"))
      (node (ref "C2") (pin "2") (pinfunction "2_2") (pintype "passive"))
      (node (ref "C20") (pin "2") (pinfunction "2_2") (pintype "passive"))
      (node (ref "C21") (pin "+") (pinfunction "+_+") (pintype "passive"))
      (node (ref "C22") (pin "2") (pinfunction "2_2") (pintype "passive"))
      (node (ref "C24") (pin "2") (pinfunction "2_2") (pintype "passive"))
      (node (ref "C25") (pin "2") (pinfunction "2_2") (pintype "passive"))
      (node (ref "C26") (pin "2") (pinfunction "2_2") (pintype "passive"))
      (node (ref "C27") (pin "2") (pinfunction "2_2") (pintype "passive"))
      (node (ref "C28") (pin "1") (pinfunction "1_1") (pintype "passive"))
      (node (ref "C29") (pin "2") (pinfunction "2_2") (pintype "passive"))
      (node (ref "C3") (pin "2") (pinfunction "2_2") (pintype "passive"))
      (node (ref "C30") (pin "2") (pinfunction "2_2") (pintype "passive"))
      (node (ref "C34") (pin "2") (pinfunction "2_2") (pintype "passive"))
      (node (ref "C35") (pin "2") (pinfunction "2_2") (pintype "passive"))
      (node (ref "C36") (pin "1") (pinfunction "1_1") (pintype "passive"))
      (node (ref "C37") (pin "1") (pinfunction "1_1") (pintype "passive"))
      (node (ref "C4") (pin "-") (pinfunction "-_-") (pintype "passive"))
      (node (ref "C41") (pin "1") (pinfunction "1_1") (pintype "passive"))
      (node (ref "C42") (pin "2") (pinfunction "2_2") (pintype "passive"))
      (node (ref "C43") (pin "2") (pinfunction "2_2") (pintype "passive"))
      (node (ref "C45") (pin "1") (pinfunction "1_1") (pintype "passive"))
      (node (ref "C47") (pin "1") (pinfunction "1_1") (pintype "passive"))
      (node (ref "C48") (pin "1") (pinfunction "1_1") (pintype "passive"))
      (node (ref "C5") (pin "-") (pinfunction "-_-") (pintype "passive"))
      (node (ref "C6") (pin "2") (pinfunction "2_2") (pintype "passive"))
      (node (ref "C7") (pin "2") (pinfunction "2_2") (pintype "passive"))
      (node (ref "C8") (pin "2") (pinfunction "2_2") (pintype "passive"))
      (node (ref "C9") (pin "1") (pinfunction "1_1") (pintype "passive"))
      (node (ref "D1") (pin "A") (pinfunction "A_A") (pintype "passive"))
      (node (ref "D2") (pin "C") (pinfunction "C_C") (pintype "passive"))
      (node (ref "D3") (pin "1") (pinfunction "A_1") (pintype "passive"))
      (node (ref "IC1") (pin "1") (pinfunction "GND_1") (pintype "power_in"))
      (node (ref "IC10") (pin "8") (pinfunction "GND_8") (pintype "power_in"))
      (node (ref "IC11") (pin "3") (pinfunction "+IN_3") (pintype "input"))
      (node (ref "IC11") (pin "5") (pinfunction "+IN_5") (pintype "input"))
      (node (ref "IC12") (pin "3") (pinfunction "+IN_3") (pintype "input"))
      (node (ref "IC12") (pin "5") (pinfunction "+IN_5") (pintype "input"))
      (node (ref "IC13") (pin "3") (pinfunction "+IN_3") (pintype "input"))
      (node (ref "IC13") (pin "5") (pinfunction "+IN_5") (pintype "input"))
      (node (ref "IC2") (pin "2") (pinfunction "A_2") (pintype "passive"))
      (node (ref "IC3") (pin "6") (pinfunction "GND_6") (pintype "power_in"))
      (node (ref "IC4") (pin "1") (pinfunction "GND_1") (pintype "power_in"))
      (node (ref "IC5") (pin "2") (pinfunction "A_2") (pintype "passive"))
      (node (ref "IC7") (pin "3") (pinfunction "+IN_3") (pintype "input"))
      (node (ref "IC7") (pin "5") (pinfunction "+IN_5") (pintype "input"))
      (node (ref "IC8") (pin "3") (pinfunction "+IN_3") (pintype "input"))
      (node (ref "IC8") (pin "5") (pinfunction "+IN_5") (pintype "input"))
      (node (ref "IC9") (pin "3") (pinfunction "+IN_3") (pintype "input"))
      (node (ref "IC9") (pin "5") (pinfunction "+IN_5") (pintype "input"))
      (node (ref "J1") (pin "GND") (pinfunction "1_GND") (pintype "passive"))
      (node (ref "J1") (pin "GND2") (pinfunction "4_GND2") (pintype "passive"))
      (node (ref "J10") (pin "GND") (pinfunction "1_GND") (pintype "passive"))
      (node (ref "J10") (pin "GND2") (pinfunction "4_GND2") (pintype "passive"))
      (node (ref "J11") (pin "GND") (pinfunction "1_GND") (pintype "passive"))
      (node (ref "J11") (pin "GND2") (pinfunction "4_GND2") (pintype "passive"))
      (node (ref "J12") (pin "GND") (pinfunction "1_GND") (pintype "passive"))
      (node (ref "J12") (pin "GND2") (pinfunction "4_GND2") (pintype "passive"))
      (node (ref "J2") (pin "GND") (pinfunction "1_GND") (pintype "passive"))
      (node (ref "J2") (pin "GND2") (pinfunction "4_GND2") (pintype "passive"))
      (node (ref "J3") (pin "GND") (pinfunction "1_GND") (pintype "passive"))
      (node (ref "J3") (pin "GND2") (pinfunction "4_GND2") (pintype "passive"))
      (node (ref "J4") (pin "GND") (pinfunction "1_GND") (pintype "passive"))
      (node (ref "J4") (pin "GND2") (pinfunction "4_GND2") (pintype "passive"))
      (node (ref "J5") (pin "GND") (pinfunction "1_GND") (pintype "passive"))
      (node (ref "J5") (pin "GND2") (pinfunction "4_GND2") (pintype "passive"))
      (node (ref "J6") (pin "GND") (pinfunction "1_GND") (pintype "passive"))
      (node (ref "J6") (pin "GND2") (pinfunction "4_GND2") (pintype "passive"))
      (node (ref "J7") (pin "GND") (pinfunction "1_GND") (pintype "passive"))
      (node (ref "J7") (pin "GND2") (pinfunction "4_GND2") (pintype "passive"))
      (node (ref "J8") (pin "GND") (pinfunction "1_GND") (pintype "passive"))
      (node (ref "J8") (pin "GND2") (pinfunction "4_GND2") (pintype "passive"))
      (node (ref "J9") (pin "GND") (pinfunction "1_GND") (pintype "passive"))
      (node (ref "J9") (pin "GND2") (pinfunction "4_GND2") (pintype "passive"))
      (node (ref "JP2") (pin "3") (pinfunction "3_3") (pintype "passive"))
      (node (ref "JP2") (pin "4") (pinfunction "4_4") (pintype "passive"))
      (node (ref "JP2") (pin "5") (pinfunction "5_5") (pintype "passive"))
      (node (ref "JP2") (pin "6") (pinfunction "6_6") (pintype "passive"))
      (node (ref "JP2") (pin "7") (pinfunction "7_7") (pintype "passive"))
      (node (ref "JP2") (pin "8") (pinfunction "8_8") (pintype "passive"))
      (node (ref "JP3") (pin "1") (pinfunction "1_1") (pintype "passive"))
      (node (ref "JP4") (pin "3") (pinfunction "3_3") (pintype "passive"))
      (node (ref "JP4") (pin "5") (pinfunction "5_5") (pintype "passive"))
      (node (ref "JP4") (pin "9") (pinfunction "9_9") (pintype "passive"))
      (node (ref "LED1") (pin "K") (pinfunction "C_K") (pintype "passive"))
      (node (ref "LED2") (pin "K") (pinfunction "C_K") (pintype "passive"))
      (node (ref "LED3") (pin "K") (pinfunction "C_K") (pintype "passive"))
      (node (ref "LED4") (pin "K") (pinfunction "C_K") (pintype "passive"))
      (node (ref "LED5") (pin "GND") (pinfunction "C_GND") (pintype "bidirectional"))
      (node (ref "LED6") (pin "K") (pinfunction "C_K") (pintype "passive"))
      (node (ref "Q2") (pin "E") (pinfunction "E_E") (pintype "passive"))
      (node (ref "R1") (pin "1") (pinfunction "1_1") (pintype "passive"))
      (node (ref "R14") (pin "P$3") (pinfunction "A_P$3") (pintype "passive"))
      (node (ref "R2") (pin "P$3") (pinfunction "A_P$3") (pintype "passive"))
      (node (ref "R24") (pin "1") (pinfunction "1_1") (pintype "passive"))
      (node (ref "R3") (pin "P$3") (pinfunction "A_P$3") (pintype "passive"))
      (node (ref "R4") (pin "P$3") (pinfunction "A_P$3") (pintype "passive"))
      (node (ref "R5") (pin "P$3") (pinfunction "A_P$3") (pintype "passive"))
      (node (ref "R65") (pin "1") (pinfunction "1_1") (pintype "passive"))
      (node (ref "SW2") (pin "A") (pinfunction "P_A") (pintype "passive"))
      (node (ref "SW2") (pin "A'") (pinfunction "P1_A'") (pintype "passive"))
      (node (ref "SW3") (pin "B1") (pinfunction "P_B1") (pintype "passive"))
      (node (ref "SW3") (pin "B2") (pinfunction "P1_B2") (pintype "passive"))
      (node (ref "SW4") (pin "B1") (pinfunction "P_B1") (pintype "passive"))
      (node (ref "SW4") (pin "B2") (pinfunction "P1_B2") (pintype "passive"))
      (node (ref "SW5") (pin "O") (pinfunction "O_O") (pintype "passive"))
      (node (ref "UC1") (pin "20") (pinfunction "PB2/BOOT1_20") (pintype "bidirectional"))
      (node (ref "UC1") (pin "23") (pinfunction "VSS_1_23") (pintype "power_in"))
      (node (ref "UC1") (pin "35") (pinfunction "VSS_2_35") (pintype "power_in"))
      (node (ref "UC1") (pin "47") (pinfunction "VSS_3_47") (pintype "power_in"))
      (node (ref "UC1") (pin "8") (pinfunction "VSS_A_8") (pintype "power_in"))
    )
    (net (code "18") (name "IN_1") (class "Default")
      (node (ref "J2") (pin "TIP") (pinfunction "2_TIP") (pintype "passive"))
      (node (ref "R54") (pin "1") (pinfunction "1_1") (pintype "passive"))
    )
    (net (code "19") (name "IN_2") (class "Default")
      (node (ref "J3") (pin "TIP") (pinfunction "2_TIP") (pintype "passive"))
      (node (ref "R33") (pin "1") (pinfunction "1_1") (pintype "passive"))
    )
    (net (code "20") (name "IN_3") (class "Default")
      (node (ref "J4") (pin "TIP") (pinfunction "2_TIP") (pintype "passive"))
      (node (ref "R36") (pin "1") (pinfunction "1_1") (pintype "passive"))
    )
    (net (code "21") (name "IN_4") (class "Default")
      (node (ref "J5") (pin "TIP") (pinfunction "2_TIP") (pintype "passive"))
      (node (ref "R57") (pin "1") (pinfunction "1_1") (pintype "passive"))
    )
    (net (code "22") (name "JTCK") (class "Default")
      (node (ref "JP4") (pin "4") (pinfunction "4_4") (pintype "passive"))
      (node (ref "UC1") (pin "37") (pinfunction "PA14/JTCK/SWCLK_37") (pintype "bidirectional"))
    )
    (net (code "23") (name "JTDI") (class "Default")
      (node (ref "JP4") (pin "8") (pinfunction "8_8") (pintype "passive"))
      (node (ref "UC1") (pin "38") (pinfunction "PA15/JTDI_38") (pintype "bidirectional"))
    )
    (net (code "24") (name "JTDO") (class "Default")
      (node (ref "JP4") (pin "6") (pinfunction "6_6") (pintype "passive"))
      (node (ref "UC1") (pin "39") (pinfunction "PB3/JTDO_39") (pintype "bidirectional"))
    )
    (net (code "25") (name "JTMS") (class "Default")
      (node (ref "JP4") (pin "2") (pinfunction "2_2") (pintype "passive"))
      (node (ref "UC1") (pin "34") (pinfunction "PA13/JTMS/SWDIO_34") (pintype "bidirectional"))
    )
    (net (code "26") (name "LED_B") (class "Default")
      (node (ref "R12") (pin "1") (pinfunction "1_1") (pintype "passive"))
      (node (ref "UC1") (pin "18") (pinfunction "PB0/ADC12_IN8/TIM3_CH3_18") (pintype "bidirectional"))
    )
    (net (code "27") (name "LED_CH1") (class "Default")
      (node (ref "R6") (pin "1") (pinfunction "1_1") (pintype "passive"))
      (node (ref "UC1") (pin "46") (pinfunction "PB9/TIM4_CH4_46") (pintype "input"))
    )
    (net (code "28") (name "LED_CH2") (class "Default")
      (node (ref "R7") (pin "1") (pinfunction "1_1") (pintype "passive"))
      (node (ref "UC1") (pin "45") (pinfunction "PB8/TIM4_CH3_45") (pintype "bidirectional"))
    )
    (net (code "29") (name "LED_CH3") (class "Default")
      (node (ref "R8") (pin "1") (pinfunction "1_1") (pintype "passive"))
      (node (ref "UC1") (pin "43") (pinfunction "PB7/I2C1_SDA/TIM4_CH2_43") (pintype "bidirectional"))
    )
    (net (code "30") (name "LED_CH4") (class "Default")
      (node (ref "R9") (pin "1") (pinfunction "1_1") (pintype "passive"))
      (node (ref "UC1") (pin "42") (pinfunction "PB6/I2C1_SCL/TIM4_CH1_42") (pintype "input"))
    )
    (net (code "31") (name "LED_FRAME") (class "Default")
      (node (ref "R16") (pin "1") (pinfunction "1_1") (pintype "passive"))
      (node (ref "UC1") (pin "41") (pinfunction "PB5/I2C1_SMBA_41") (pintype "input"))
    )
    (net (code "32") (name "LED_G") (class "Default")
      (node (ref "R11") (pin "1") (pinfunction "1_1") (pintype "passive"))
      (node (ref "UC1") (pin "17") (pinfunction "PA7/SPI1_MOSI/ADC12_IN7/TIM3_CH2_17") (pintype "bidirectional"))
    )
    (net (code "33") (name "LED_R") (class "Default")
      (node (ref "R13") (pin "1") (pinfunction "1_1") (pintype "passive"))
      (node (ref "UC1") (pin "19") (pinfunction "PB1/ADC12_IN9/TIM3_CH4_19") (pintype "bidirectional"))
    )
    (net (code "34") (name "MODULATION") (class "Default")
      (node (ref "D3") (pin "3") (pinfunction "AC_3") (pintype "passive"))
      (node (ref "R39") (pin "1") (pinfunction "1_1") (pintype "passive"))
      (node (ref "UC1") (pin "14") (pinfunction "PA4/SPI1_NSS/USART2_CK/ADC12_IN4_14") (pintype "bidirectional"))
    )
    (net (code "35") (name "Net-(C22-Pad1)") (class "Default")
      (node (ref "C22") (pin "1") (pinfunction "1_1") (pintype "passive"))
      (node (ref "R34") (pin "1") (pinfunction "1_1") (pintype "passive"))
    )
    (net (code "36") (name "Net-(C27-Pad1)") (class "Default")
      (node (ref "C27") (pin "1") (pinfunction "1_1") (pintype "passive"))
      (node (ref "R35") (pin "1") (pinfunction "1_1") (pintype "passive"))
    )
    (net (code "37") (name "Net-(C42-Pad1)") (class "Default")
      (node (ref "C42") (pin "1") (pinfunction "1_1") (pintype "passive"))
      (node (ref "R55") (pin "1") (pinfunction "1_1") (pintype "passive"))
    )
    (net (code "38") (name "Net-(C43-Pad1)") (class "Default")
      (node (ref "C43") (pin "1") (pinfunction "1_1") (pintype "passive"))
      (node (ref "R56") (pin "1") (pinfunction "1_1") (pintype "passive"))
    )
    (net (code "39") (name "Net-(IC3-OUTA)") (class "Default")
      (node (ref "IC3") (pin "2") (pinfunction "OUTA_2") (pintype "output"))
      (node (ref "R19") (pin "1") (pinfunction "1_1") (pintype "passive"))
    )
    (net (code "40") (name "Net-(IC3-OUTB)") (class "Default")
      (node (ref "IC3") (pin "3") (pinfunction "OUTB_3") (pintype "output"))
      (node (ref "R20") (pin "1") (pinfunction "1_1") (pintype "passive"))
    )
    (net (code "41") (name "Net-(IC3-OUTC)") (class "Default")
      (node (ref "IC3") (pin "4") (pinfunction "OUTC_4") (pintype "output"))
      (node (ref "R21") (pin "1") (pinfunction "1_1") (pintype "passive"))
    )
    (net (code "42") (name "Net-(IC3-OUTD)") (class "Default")
      (node (ref "IC3") (pin "5") (pinfunction "OUTD_5") (pintype "output"))
      (node (ref "R22") (pin "1") (pinfunction "1_1") (pintype "passive"))
    )
    (net (code "43") (name "Net-(IC5-C)") (class "Default")
      (node (ref "IC5") (pin "1") (pinfunction "C_1") (pintype "passive"))
      (node (ref "IC6") (pin "5") (pinfunction "+IN_5") (pintype "input"))
      (node (ref "R26") (pin "2") (pinfunction "2_2") (pintype "passive"))
      (node (ref "R27") (pin "2") (pinfunction "2_2") (pintype "passive"))
    )
    (net (code "44") (name "Net-(IC6A-+IN)") (class "Default")
      (node (ref "IC6") (pin "3") (pinfunction "+IN_3") (pintype "input"))
      (node (ref "R27") (pin "1") (pinfunction "1_1") (pintype "passive"))
      (node (ref "R65") (pin "2") (pinfunction "2_2") (pintype "passive"))
    )
    (net (code "45") (name "Net-(IC7A--IN)") (class "Default")
      (node (ref "C38") (pin "1") (pinfunction "1_1") (pintype "passive"))
      (node (ref "IC7") (pin "2") (pinfunction "-IN_2") (pintype "input"))
      (node (ref "R43") (pin "1") (pinfunction "1_1") (pintype "passive"))
      (node (ref "R44") (pin "2") (pinfunction "2_2") (pintype "passive"))
      (node (ref "R45") (pin "2") (pinfunction "2_2") (pintype "passive"))
      (node (ref "R46") (pin "2") (pinfunction "2_2") (pintype "passive"))
      (node (ref "R47") (pin "2") (pinfunction "2_2") (pintype "passive"))
    )
    (net (code "46") (name "Net-(IC7A-OUT)") (class "Default")
      (node (ref "C38") (pin "2") (pinfunction "2_2") (pintype "passive"))
      (node (ref "IC7") (pin "1") (pinfunction "OUT_1") (pintype "output"))
      (node (ref "R30") (pin "1") (pinfunction "1_1") (pintype "passive"))
      (node (ref "R43") (pin "2") (pinfunction "2_2") (pintype "passive"))
    )
    (net (code "47") (name "Net-(IC7B--IN)") (class "Default")
      (node (ref "C23") (pin "1") (pinfunction "1_1") (pintype "passive"))
      (node (ref "IC7") (pin "6") (pinfunction "-IN_6") (pintype "input"))
      (node (ref "R29") (pin "1") (pinfunction "1_1") (pintype "passive"))
      (node (ref "R30") (pin "2") (pinfunction "2_2") (pintype "passive"))
    )
    (net (code "48") (name "Net-(IC7B-OUT)") (class "Default")
      (node (ref "C23") (pin "2") (pinfunction "2_2") (pintype "passive"))
      (node (ref "IC7") (pin "7") (pinfunction "OUT_7") (pintype "output"))
      (node (ref "R28") (pin "1") (pinfunction "1_1") (pintype "passive"))
      (node (ref "R29") (pin "2") (pinfunction "2_2") (pintype "passive"))
    )
    (net (code "49") (name "Net-(IC8A--IN)") (class "Default")
      (node (ref "C39") (pin "1") (pinfunction "1_1") (pintype "passive"))
      (node (ref "IC8") (pin "2") (pinfunction "-IN_2") (pintype "input"))
      (node (ref "R49") (pin "1") (pinfunction "1_1") (pintype "passive"))
      (node (ref "R50") (pin "2") (pinfunction "2_2") (pintype "passive"))
    )
    (net (code "50") (name "Net-(IC8A-OUT)") (class "Default")
      (node (ref "C39") (pin "2") (pinfunction "2_2") (pintype "passive"))
      (node (ref "IC8") (pin "1") (pinfunction "OUT_1") (pintype "output"))
      (node (ref "R48") (pin "1") (pinfunction "1_1") (pintype "passive"))
      (node (ref "R49") (pin "2") (pinfunction "2_2") (pintype "passive"))
    )
    (net (code "51") (name "Net-(IC8B-OUT)") (class "Default")
      (node (ref "IC8") (pin "7") (pinfunction "OUT_7") (pintype "output"))
      (node (ref "R31") (pin "2") (pinfunction "2_2") (pintype "passive"))
      (node (ref "R50") (pin "1") (pinfunction "1_1") (pintype "passive"))
    )
    (net (code "52") (name "Net-(IC9A--IN)") (class "Default")
      (node (ref "C40") (pin "1") (pinfunction "1_1") (pintype "passive"))
      (node (ref "IC9") (pin "2") (pinfunction "-IN_2") (pintype "input"))
      (node (ref "R52") (pin "1") (pinfunction "1_1") (pintype "passive"))
      (node (ref "R53") (pin "2") (pinfunction "2_2") (pintype "passive"))
    )
    (net (code "53") (name "Net-(IC9A-OUT)") (class "Default")
      (node (ref "C40") (pin "2") (pinfunction "2_2") (pintype "passive"))
      (node (ref "IC9") (pin "1") (pinfunction "OUT_1") (pintype "output"))
      (node (ref "R51") (pin "1") (pinfunction "1_1") (pintype "passive"))
      (node (ref "R52") (pin "2") (pinfunction "2_2") (pintype "passive"))
    )
    (net (code "54") (name "Net-(IC9B-OUT)") (class "Default")
      (node (ref "IC9") (pin "7") (pinfunction "OUT_7") (pintype "output"))
      (node (ref "R32") (pin "2") (pinfunction "2_2") (pintype "passive"))
      (node (ref "R53") (pin "1") (pinfunction "1_1") (pintype "passive"))
    )
    (net (code "55") (name "Net-(IC10A-IN)") (class "Default")
      (node (ref "IC10") (pin "2") (pinfunction "IN_2") (pintype "input"))
      (node (ref "R54") (pin "2") (pinfunction "2_2") (pintype "passive"))
      (node (ref "R55") (pin "2") (pinfunction "2_2") (pintype "passive"))
    )
    (net (code "56") (name "Net-(IC10A-OUT)") (class "Default")
      (node (ref "IC10") (pin "4") (pinfunction "OUT_4") (pintype "output"))
      (node (ref "IC8") (pin "6") (pinfunction "-IN_6") (pintype "input"))
      (node (ref "R31") (pin "1") (pinfunction "1_1") (pintype "passive"))
    )
    (net (code "57") (name "Net-(IC10B-IN)") (class "Default")
      (node (ref "IC10") (pin "7") (pinfunction "IN_7") (pintype "input"))
      (node (ref "R56") (pin "2") (pinfunction "2_2") (pintype "passive"))
      (node (ref "R57") (pin "2") (pinfunction "2_2") (pintype "passive"))
    )
    (net (code "58") (name "Net-(IC10B-OUT)") (class "Default")
      (node (ref "IC10") (pin "5") (pinfunction "OUT_5") (pintype "output"))
      (node (ref "IC12") (pin "6") (pinfunction "-IN_6") (pintype "input"))
      (node (ref "R38") (pin "1") (pinfunction "1_1") (pintype "passive"))
    )
    (net (code "59") (name "Net-(IC10C-IN)") (class "Default")
      (node (ref "IC10") (pin "10") (pinfunction "IN_10") (pintype "input"))
      (node (ref "R35") (pin "2") (pinfunction "2_2") (pintype "passive"))
      (node (ref "R36") (pin "2") (pinfunction "2_2") (pintype "passive"))
    )
    (net (code "60") (name "Net-(IC10C-OUT)") (class "Default")
      (node (ref "IC10") (pin "12") (pinfunction "OUT_12") (pintype "output"))
      (node (ref "IC11") (pin "6") (pinfunction "-IN_6") (pintype "input"))
      (node (ref "R37") (pin "1") (pinfunction "1_1") (pintype "passive"))
    )
    (net (code "61") (name "Net-(IC10D-IN)") (class "Default")
      (node (ref "IC10") (pin "15") (pinfunction "IN_15") (pintype "input"))
      (node (ref "R33") (pin "2") (pinfunction "2_2") (pintype "passive"))
      (node (ref "R34") (pin "2") (pinfunction "2_2") (pintype "passive"))
    )
    (net (code "62") (name "Net-(IC10D-OUT)") (class "Default")
      (node (ref "IC10") (pin "13") (pinfunction "OUT_13") (pintype "output"))
      (node (ref "IC9") (pin "6") (pinfunction "-IN_6") (pintype "input"))
      (node (ref "R32") (pin "1") (pinfunction "1_1") (pintype "passive"))
    )
    (net (code "63") (name "Net-(IC11A--IN)") (class "Default")
      (node (ref "C44") (pin "1") (pinfunction "1_1") (pintype "passive"))
      (node (ref "IC11") (pin "2") (pinfunction "-IN_2") (pintype "input"))
      (node (ref "R59") (pin "1") (pinfunction "1_1") (pintype "passive"))
      (node (ref "R60") (pin "2") (pinfunction "2_2") (pintype "passive"))
    )
    (net (code "64") (name "Net-(IC11A-OUT)") (class "Default")
      (node (ref "C44") (pin "2") (pinfunction "2_2") (pintype "passive"))
      (node (ref "IC11") (pin "1") (pinfunction "OUT_1") (pintype "output"))
      (node (ref "R58") (pin "1") (pinfunction "1_1") (pintype "passive"))
      (node (ref "R59") (pin "2") (pinfunction "2_2") (pintype "passive"))
    )
    (net (code "65") (name "Net-(IC11B-OUT)") (class "Default")
      (node (ref "IC11") (pin "7") (pinfunction "OUT_7") (pintype "output"))
      (node (ref "R37") (pin "2") (pinfunction "2_2") (pintype "passive"))
      (node (ref "R60") (pin "1") (pinfunction "1_1") (pintype "passive"))
    )
    (net (code "66") (name "Net-(IC12A--IN)") (class "Default")
      (node (ref "C46") (pin "1") (pinfunction "1_1") (pintype "passive"))
      (node (ref "IC12") (pin "2") (pinfunction "-IN_2") (pintype "input"))
      (node (ref "R62") (pin "1") (pinfunction "1_1") (pintype "passive"))
      (node (ref "R63") (pin "2") (pinfunction "2_2") (pintype "passive"))
    )
    (net (code "67") (name "Net-(IC12A-OUT)") (class "Default")
      (node (ref "C46") (pin "2") (pinfunction "2_2") (pintype "passive"))
      (node (ref "IC12") (pin "1") (pinfunction "OUT_1") (pintype "output"))
      (node (ref "R61") (pin "1") (pinfunction "1_1") (pintype "passive"))
      (node (ref "R62") (pin "2") (pinfunction "2_2") (pintype "passive"))
    )
    (net (code "68") (name "Net-(IC12B-OUT)") (class "Default")
      (node (ref "IC12") (pin "7") (pinfunction "OUT_7") (pintype "output"))
      (node (ref "R38") (pin "2") (pinfunction "2_2") (pintype "passive"))
      (node (ref "R63") (pin "1") (pinfunction "1_1") (pintype "passive"))
    )
    (net (code "69") (name "Net-(IC13A--IN)") (class "Default")
      (node (ref "IC13") (pin "2") (pinfunction "-IN_2") (pintype "input"))
      (node (ref "R15") (pin "P$1") (pinfunction "E_P$1") (pintype "passive"))
      (node (ref "R64") (pin "2") (pinfunction "2_2") (pintype "passive"))
    )
    (net (code "70") (name "Net-(IC13A-OUT)") (class "Default")
      (node (ref "IC13") (pin "1") (pinfunction "OUT_1") (pintype "output"))
      (node (ref "R41") (pin "2") (pinfunction "2_2") (pintype "passive"))
      (node (ref "R64") (pin "1") (pinfunction "1_1") (pintype "passive"))
    )
    (net (code "71") (name "Net-(IC13B--IN)") (class "Default")
      (node (ref "C31") (pin "1") (pinfunction "1_1") (pintype "passive"))
      (node (ref "IC13") (pin "6") (pinfunction "-IN_6") (pintype "input"))
      (node (ref "R15") (pin "P$3") (pinfunction "A_P$3") (pintype "passive"))
      (node (ref "R40") (pin "2") (pinfunction "2_2") (pintype "passive"))
      (node (ref "R41") (pin "1") (pinfunction "1_1") (pintype "passive"))
      (node (ref "R42") (pin "1") (pinfunction "1_1") (pintype "passive"))
    )
    (net (code "72") (name "Net-(IC13B-OUT)") (class "Default")
      (node (ref "C31") (pin "2") (pinfunction "2_2") (pintype "passive"))
      (node (ref "IC13") (pin "7") (pinfunction "OUT_7") (pintype "output"))
      (node (ref "R39") (pin "2") (pinfunction "2_2") (pintype "passive"))
      (node (ref "R40") (pin "1") (pinfunction "1_1") (pintype "passive"))
    )
    (net (code "73") (name "Net-(J1-3)") (class "Default")
      (node (ref "J1") (pin "SW") (pinfunction "3_SW") (pintype "passive"))
      (node (ref "SW5") (pin "P") (pinfunction "P_P") (pintype "passive"))
    )
    (net (code "74") (name "Net-(J6-2)") (class "Default")
      (node (ref "J6") (pin "TIP") (pinfunction "2_TIP") (pintype "passive"))
      (node (ref "R18") (pin "1") (pinfunction "1_1") (pintype "passive"))
    )
    (net (code "75") (name "Net-(J7-2)") (class "Default")
      (node (ref "J7") (pin "TIP") (pinfunction "2_TIP") (pintype "passive"))
      (node (ref "R28") (pin "2") (pinfunction "2_2") (pintype "passive"))
    )
    (net (code "76") (name "Net-(J8-2)") (class "Default")
      (node (ref "J8") (pin "TIP") (pinfunction "2_TIP") (pintype "passive"))
      (node (ref "R48") (pin "2") (pinfunction "2_2") (pintype "passive"))
    )
    (net (code "77") (name "Net-(J9-2)") (class "Default")
      (node (ref "J9") (pin "TIP") (pinfunction "2_TIP") (pintype "passive"))
      (node (ref "R51") (pin "2") (pinfunction "2_2") (pintype "passive"))
    )
    (net (code "78") (name "Net-(J10-2)") (class "Default")
      (node (ref "J10") (pin "TIP") (pinfunction "2_TIP") (pintype "passive"))
      (node (ref "R58") (pin "2") (pinfunction "2_2") (pintype "passive"))
    )
    (net (code "79") (name "Net-(J11-2)") (class "Default")
      (node (ref "J11") (pin "TIP") (pinfunction "2_TIP") (pintype "passive"))
      (node (ref "R61") (pin "2") (pinfunction "2_2") (pintype "passive"))
    )
    (net (code "80") (name "Net-(J12-2)") (class "Default")
      (node (ref "J12") (pin "TIP") (pinfunction "2_TIP") (pintype "passive"))
      (node (ref "Q2") (pin "C") (pinfunction "C_C") (pintype "passive"))
      (node (ref "R24") (pin "2") (pinfunction "2_2") (pintype "passive"))
      (node (ref "R25") (pin "1") (pinfunction "1_1") (pintype "passive"))
    )
    (net (code "81") (name "Net-(JP1-Pad2)") (class "Default")
      (node (ref "JP1") (pin "2") (pinfunction "2_2") (pintype "passive"))
      (node (ref "SW5") (pin "S") (pinfunction "S_S") (pintype "passive"))
    )
    (net (code "82") (name "Net-(JP2-Pad1)") (class "Default")
      (node (ref "JP2") (pin "1") (pinfunction "1_1") (pintype "passive"))
      (node (ref "JP2") (pin "2") (pinfunction "2_2") (pintype "passive"))
      (node (ref "P1") (pin "2") (pinfunction "2_2") (pintype "bidirectional"))
    )
    (net (code "83") (name "Net-(JP2-Pad10)") (class "Default")
      (node (ref "JP2") (pin "10") (pinfunction "10_10") (pintype "passive"))
      (node (ref "JP2") (pin "9") (pinfunction "9_9") (pintype "passive"))
      (node (ref "P2") (pin "2") (pinfunction "2_2") (pintype "bidirectional"))
    )
    (net (code "84") (name "Net-(LED1-PadA)") (class "Default")
      (node (ref "LED1") (pin "A") (pinfunction "A_A") (pintype "passive"))
      (node (ref "R6") (pin "2") (pinfunction "2_2") (pintype "passive"))
    )
    (net (code "85") (name "Net-(LED2-PadA)") (class "Default")
      (node (ref "LED2") (pin "A") (pinfunction "A_A") (pintype "passive"))
      (node (ref "R7") (pin "2") (pinfunction "2_2") (pintype "passive"))
    )
    (net (code "86") (name "Net-(LED3-PadA)") (class "Default")
      (node (ref "LED3") (pin "A") (pinfunction "A_A") (pintype "passive"))
      (node (ref "R8") (pin "2") (pinfunction "2_2") (pintype "passive"))
    )
    (net (code "87") (name "Net-(LED4-PadA)") (class "Default")
      (node (ref "LED4") (pin "A") (pinfunction "A_A") (pintype "passive"))
      (node (ref "R9") (pin "2") (pinfunction "2_2") (pintype "passive"))
    )
    (net (code "88") (name "Net-(LED5-PadBLU)") (class "Default")
      (node (ref "LED5") (pin "BLU") (pinfunction "BLU_BLU") (pintype "bidirectional"))
      (node (ref "R12") (pin "2") (pinfunction "2_2") (pintype "passive"))
    )
    (net (code "89") (name "Net-(LED5-PadGRN)") (class "Default")
      (node (ref "LED5") (pin "GRN") (pinfunction "GRN_GRN") (pintype "bidirectional"))
      (node (ref "R11") (pin "2") (pinfunction "2_2") (pintype "passive"))
    )
    (net (code "90") (name "Net-(LED5-PadRED)") (class "Default")
      (node (ref "LED5") (pin "RED") (pinfunction "RED_RED") (pintype "bidirectional"))
      (node (ref "R13") (pin "2") (pinfunction "2_2") (pintype "passive"))
    )
    (net (code "91") (name "Net-(LED6-PadA)") (class "Default")
      (node (ref "LED6") (pin "A") (pinfunction "A_A") (pintype "passive"))
      (node (ref "R16") (pin "2") (pinfunction "2_2") (pintype "passive"))
    )
    (net (code "92") (name "Net-(Q2-PadB)") (class "Default")
      (node (ref "Q2") (pin "B") (pinfunction "B_B") (pintype "passive"))
      (node (ref "R23") (pin "2") (pinfunction "2_2") (pintype "passive"))
    )
    (net (code "93") (name "Net-(R15-S)") (class "Default")
      (node (ref "R15") (pin "P$2") (pinfunction "S_P$2") (pintype "passive"))
      (node (ref "R18") (pin "2") (pinfunction "2_2") (pintype "passive"))
    )
    (net (code "94") (name "Net-(UC1-PD0-OSC_IN)") (class "Default")
      (node (ref "C1") (pin "2") (pinfunction "2_2") (pintype "passive"))
      (node (ref "Q1") (pin "2") (pinfunction "2_2") (pintype "passive"))
      (node (ref "UC1") (pin "5") (pinfunction "PD0-OSC_IN_5") (pintype "input"))
    )
    (net (code "95") (name "Net-(UC1-PD1-OSC_OUT)") (class "Default")
      (node (ref "C9") (pin "2") (pinfunction "2_2") (pintype "passive"))
      (node (ref "Q1") (pin "1") (pinfunction "1_1") (pintype "passive"))
      (node (ref "UC1") (pin "6") (pinfunction "PD1-OSC_OUT_6") (pintype "input"))
    )
    (net (code "96") (name "PAN") (class "Default")
      (node (ref "J1") (pin "TIP") (pinfunction "2_TIP") (pintype "passive"))
      (node (ref "J2") (pin "SW") (pinfunction "3_SW") (pintype "passive"))
      (node (ref "J3") (pin "SW") (pinfunction "3_SW") (pintype "passive"))
      (node (ref "J4") (pin "SW") (pinfunction "3_SW") (pintype "passive"))
      (node (ref "J5") (pin "SW") (pinfunction "3_SW") (pintype "passive"))
    )
    (net (code "97") (name "POT_CH1") (class "Default")
      (node (ref "R2") (pin "P$2") (pinfunction "S_P$2") (pintype "passive"))
      (node (ref "UC1") (pin "10") (pinfunction "PA0_WKUP/USART2_CTS/ADC12_IN0/TIM2_CH1_ETR_10") (pintype "bidirectional"))
    )
    (net (code "98") (name "POT_CH2") (class "Default")
      (node (ref "R3") (pin "P$2") (pinfunction "S_P$2") (pintype "passive"))
      (node (ref "UC1") (pin "11") (pinfunction "PA1/USART2_RTS/ADC12_IN1/TIM2_CH2_11") (pintype "bidirectional"))
    )
    (net (code "99") (name "POT_CH3") (class "Default")
      (node (ref "R4") (pin "P$2") (pinfunction "S_P$2") (pintype "passive"))
      (node (ref "UC1") (pin "12") (pinfunction "PA2/USART2_TX/ADC12_IN2/TIM2_CH3_12") (pintype "bidirectional"))
    )
    (net (code "100") (name "POT_CH4") (class "Default")
      (node (ref "R5") (pin "P$2") (pinfunction "S_P$2") (pintype "passive"))
      (node (ref "UC1") (pin "13") (pinfunction "PA3/USART2_RX/ADC12_IN3/TIM2_CH4_13") (pintype "bidirectional"))
    )
    (net (code "101") (name "POT_FRAME") (class "Default")
      (node (ref "R14") (pin "P$2") (pinfunction "S_P$2") (pintype "passive"))
      (node (ref "UC1") (pin "15") (pinfunction "PA5/SPI1_SCK/ADC12_IN5_15") (pintype "bidirectional"))
    )
    (net (code "102") (name "RESET") (class "Default")
      (node (ref "JP4") (pin "10") (pinfunction "10_10") (pintype "passive"))
      (node (ref "R10") (pin "1") (pinfunction "1_1") (pintype "passive"))
      (node (ref "SW2") (pin "B") (pinfunction "S_B") (pintype "passive"))
      (node (ref "SW2") (pin "B'") (pinfunction "S1_B'") (pintype "passive"))
      (node (ref "UC1") (pin "7") (pinfunction "NRST_7") (pintype "input"))
    )
    (net (code "103") (name "RX") (class "Default")
      (node (ref "JP3") (pin "4") (pinfunction "4_4") (pintype "passive"))
      (node (ref "UC1") (pin "31") (pinfunction "PA10/USART1_RX/TIM1_CH3_31") (pintype "bidirectional"))
    )
    (net (code "104") (name "TX") (class "Default")
      (node (ref "JP3") (pin "5") (pinfunction "5_5") (pintype "passive"))
      (node (ref "UC1") (pin "30") (pinfunction "PA9/USART1_TX/TIM1_CH2_30") (pintype "input"))
    )
    (net (code "105") (name "VCA_1") (class "Default")
      (node (ref "J8") (pin "SW") (pinfunction "3_SW") (pintype "passive"))
      (node (ref "R44") (pin "1") (pinfunction "1_1") (pintype "passive"))
    )
    (net (code "106") (name "VCA_2") (class "Default")
      (node (ref "J9") (pin "SW") (pinfunction "3_SW") (pintype "passive"))
      (node (ref "R47") (pin "1") (pinfunction "1_1") (pintype "passive"))
    )
    (net (code "107") (name "VCA_3") (class "Default")
      (node (ref "J10") (pin "SW") (pinfunction "3_SW") (pintype "passive"))
      (node (ref "R46") (pin "1") (pinfunction "1_1") (pintype "passive"))
    )
    (net (code "108") (name "VCA_4") (class "Default")
      (node (ref "J11") (pin "SW") (pinfunction "3_SW") (pintype "passive"))
      (node (ref "R45") (pin "1") (pinfunction "1_1") (pintype "passive"))
    )
    (net (code "109") (name "VCC") (class "Default")
      (node (ref "C11") (pin "+") (pinfunction "+_+") (pintype "passive"))
      (node (ref "C24") (pin "1") (pinfunction "1_1") (pintype "passive"))
      (node (ref "C25") (pin "1") (pinfunction "1_1") (pintype "passive"))
      (node (ref "C26") (pin "1") (pinfunction "1_1") (pintype "passive"))
      (node (ref "C29") (pin "1") (pinfunction "1_1") (pintype "passive"))
      (node (ref "C30") (pin "1") (pinfunction "1_1") (pintype "passive"))
      (node (ref "C34") (pin "1") (pinfunction "1_1") (pintype "passive"))
      (node (ref "C35") (pin "1") (pinfunction "1_1") (pintype "passive"))
      (node (ref "C4") (pin "+") (pinfunction "+_+") (pintype "passive"))
      (node (ref "D1") (pin "C") (pinfunction "C_C") (pintype "passive"))
      (node (ref "IC1") (pin "3") (pinfunction "VIN_3") (pintype "input"))
      (node (ref "IC10") (pin "16") (pinfunction "V+_16") (pintype "power_in"))
      (node (ref "IC11") (pin "8") (pinfunction "V+_8") (pintype "power_in"))
      (node (ref "IC12") (pin "8") (pinfunction "V+_8") (pintype "power_in"))
      (node (ref "IC13") (pin "8") (pinfunction "V+_8") (pintype "power_in"))
      (node (ref "IC4") (pin "3") (pinfunction "VIN_3") (pintype "input"))
      (node (ref "IC6") (pin "8") (pinfunction "V+_8") (pintype "power_in"))
      (node (ref "IC7") (pin "8") (pinfunction "V+_8") (pintype "power_in"))
      (node (ref "IC8") (pin "8") (pinfunction "V+_8") (pintype "power_in"))
      (node (ref "IC9") (pin "8") (pinfunction "V+_8") (pintype "power_in"))
      (node (ref "P1") (pin "1") (pinfunction "1_1") (pintype "bidirectional"))
      (node (ref "R25") (pin "2") (pinfunction "2_2") (pintype "passive"))
      (node (ref "R26") (pin "1") (pinfunction "1_1") (pintype "passive"))
    )
    (net (code "110") (name "VEE") (class "Default")
      (node (ref "C21") (pin "-") (pinfunction "-_-") (pintype "passive"))
      (node (ref "C28") (pin "2") (pinfunction "2_2") (pintype "passive"))
      (node (ref "C36") (pin "2") (pinfunction "2_2") (pintype "passive"))
      (node (ref "C37") (pin "2") (pinfunction "2_2") (pintype "passive"))
      (node (ref "C41") (pin "2") (pinfunction "2_2") (pintype "passive"))
      (node (ref "C45") (pin "2") (pinfunction "2_2") (pintype "passive"))
      (node (ref "C47") (pin "2") (pinfunction "2_2") (pintype "passive"))
      (node (ref "C48") (pin "2") (pinfunction "2_2") (pintype "passive"))
      (node (ref "D2") (pin "A") (pinfunction "A_A") (pintype "passive"))
      (node (ref "IC10") (pin "9") (pinfunction "V-_9") (pintype "power_in"))
      (node (ref "IC11") (pin "4") (pinfunction "V-_4") (pintype "power_in"))
      (node (ref "IC12") (pin "4") (pinfunction "V-_4") (pintype "power_in"))
      (node (ref "IC13") (pin "4") (pinfunction "V-_4") (pintype "power_in"))
      (node (ref "IC6") (pin "4") (pinfunction "V-_4") (pintype "power_in"))
      (node (ref "IC7") (pin "4") (pinfunction "V-_4") (pintype "power_in"))
      (node (ref "IC8") (pin "4") (pinfunction "V-_4") (pintype "power_in"))
      (node (ref "IC9") (pin "4") (pinfunction "V-_4") (pintype "power_in"))
      (node (ref "P2") (pin "1") (pinfunction "1_1") (pintype "bidirectional"))
      (node (ref "R42") (pin "2") (pinfunction "2_2") (pintype "passive"))
    )
    (net (code "111") (name "unconnected-(IC10E-MODE-Pad1)") (class "Default")
      (node (ref "IC10") (pin "1") (pinfunction "MODE_1") (pintype "input"))
    )
    (net (code "112") (name "unconnected-(J6-3-PadSW)") (class "Default")
      (node (ref "J6") (pin "SW") (pinfunction "3_SW") (pintype "passive"))
    )
    (net (code "113") (name "unconnected-(J7-3-PadSW)") (class "Default")
      (node (ref "J7") (pin "SW") (pinfunction "3_SW") (pintype "passive"))
    )
    (net (code "114") (name "unconnected-(J12-3-PadSW)") (class "Default")
      (node (ref "J12") (pin "SW") (pinfunction "3_SW") (pintype "passive"))
    )
    (net (code "115") (name "unconnected-(JP3-Pad2)") (class "Default")
      (node (ref "JP3") (pin "2") (pinfunction "2_2") (pintype "passive"))
    )
    (net (code "116") (name "unconnected-(JP3-Pad3)") (class "Default")
      (node (ref "JP3") (pin "3") (pinfunction "3_3") (pintype "passive"))
    )
    (net (code "117") (name "unconnected-(JP3-Pad6)") (class "Default")
      (node (ref "JP3") (pin "6") (pinfunction "6_6") (pintype "passive"))
    )
    (net (code "118") (name "unconnected-(JP4-Pad7)") (class "Default")
      (node (ref "JP4") (pin "7") (pinfunction "7_7") (pintype "passive"))
    )
    (net (code "119") (name "unconnected-(UC1-PA8{slash}USART1_CK{slash}TIM1_CH1{slash}MCO-Pad29)") (class "Default")
      (node (ref "UC1") (pin "29") (pinfunction "PA8/USART1_CK/TIM1_CH1/MCO_29") (pintype "bidirectional"))
    )
    (net (code "120") (name "unconnected-(UC1-PA11{slash}USART1_CTS{slash}CAN_RX{slash}TIM1_CH4{slash}USBDM-Pad32)") (class "Default")
      (node (ref "UC1") (pin "32") (pinfunction "PA11/USART1_CTS/CAN_RX/TIM1_CH4/USBDM_32") (pintype "bidirectional"))
    )
    (net (code "121") (name "unconnected-(UC1-PA12{slash}USART1_RTS{slash}CAN_TX{slash}TIM1_ETR{slash}USBDP-Pad33)") (class "Default")
      (node (ref "UC1") (pin "33") (pinfunction "PA12/USART1_RTS/CAN_TX/TIM1_ETR/USBDP_33") (pintype "bidirectional"))
    )
    (net (code "122") (name "unconnected-(UC1-PB4{slash}NJTRST-Pad40)") (class "Default")
      (node (ref "UC1") (pin "40") (pinfunction "PB4/NJTRST_40") (pintype "bidirectional"))
    )
    (net (code "123") (name "unconnected-(UC1-PB14{slash}SPI2_MISO{slash}USART3_RTS{slash}TIM1_CH2N-Pad27)") (class "Default")
      (node (ref "UC1") (pin "27") (pinfunction "PB14/SPI2_MISO/USART3_RTS/TIM1_CH2N_27") (pintype "input"))
    )
    (net (code "124") (name "unconnected-(UC1-PC13-TAMPER-RTC-Pad2)") (class "Default")
      (node (ref "UC1") (pin "2") (pinfunction "PC13-TAMPER-RTC_2") (pintype "input"))
    )
    (net (code "125") (name "unconnected-(UC1-PC14-OSC32_IN-Pad3)") (class "Default")
      (node (ref "UC1") (pin "3") (pinfunction "PC14-OSC32_IN_3") (pintype "input"))
    )
    (net (code "126") (name "unconnected-(UC1-PC15-OSC32_OUT-Pad4)") (class "Default")
      (node (ref "UC1") (pin "4") (pinfunction "PC15-OSC32_OUT_4") (pintype "input"))
    )
  )
)
